# SOM_EVAL_BOARD_V100.net
KiCad netlist of a schematic drawn in EAGLE
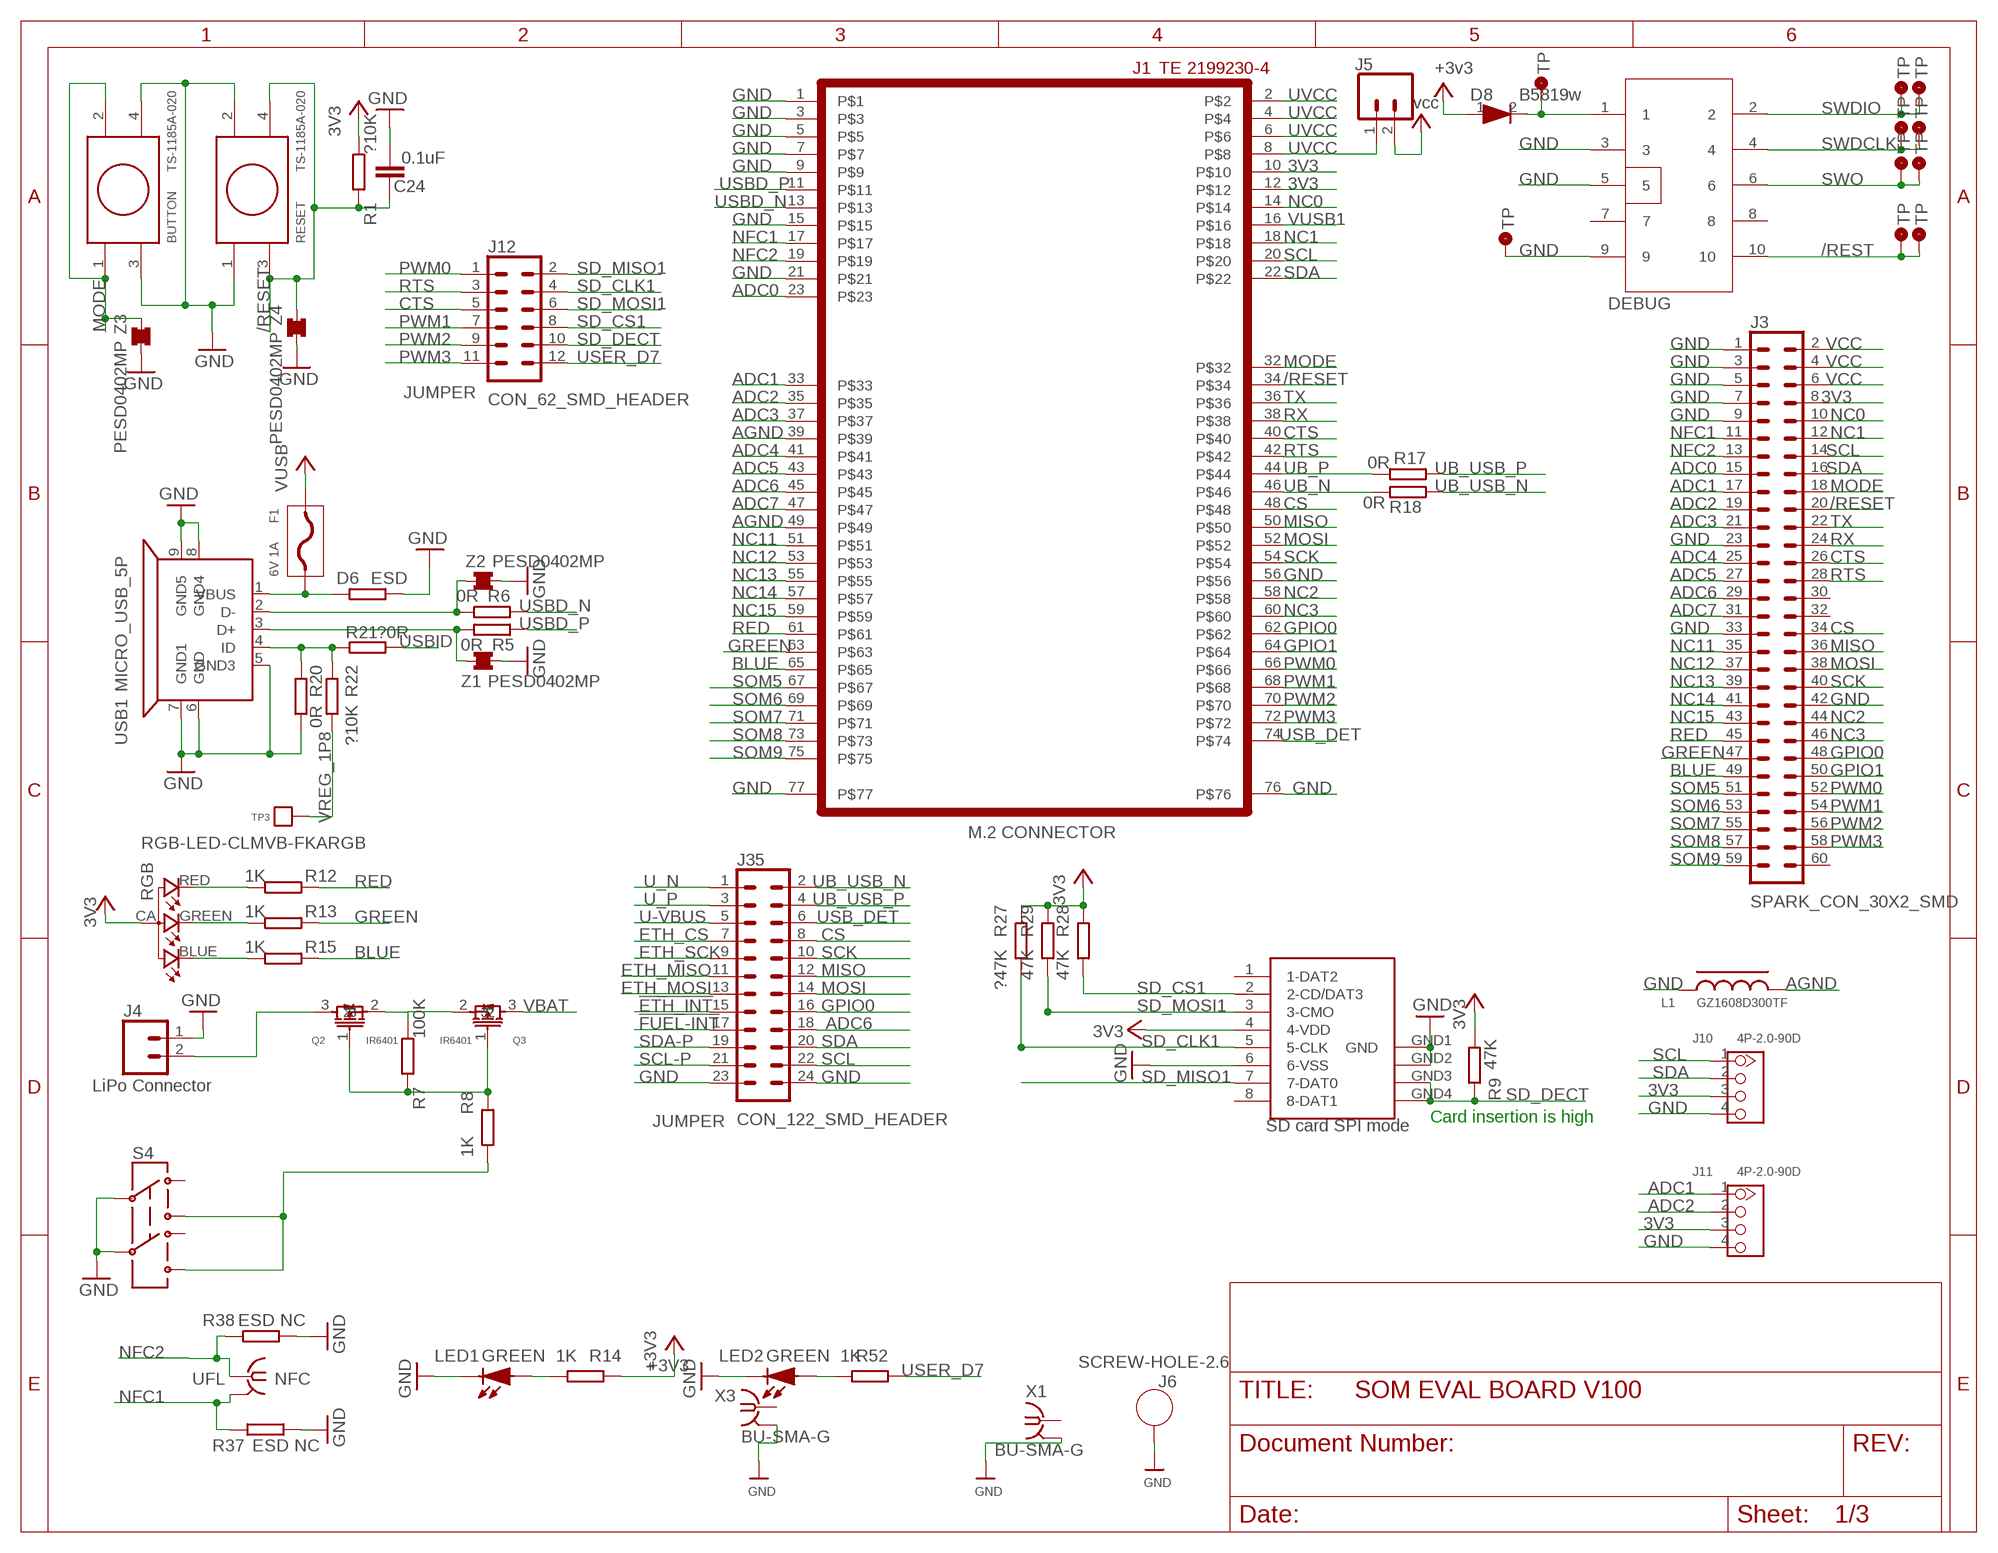
[diagram p0: schematic, sheet 1]
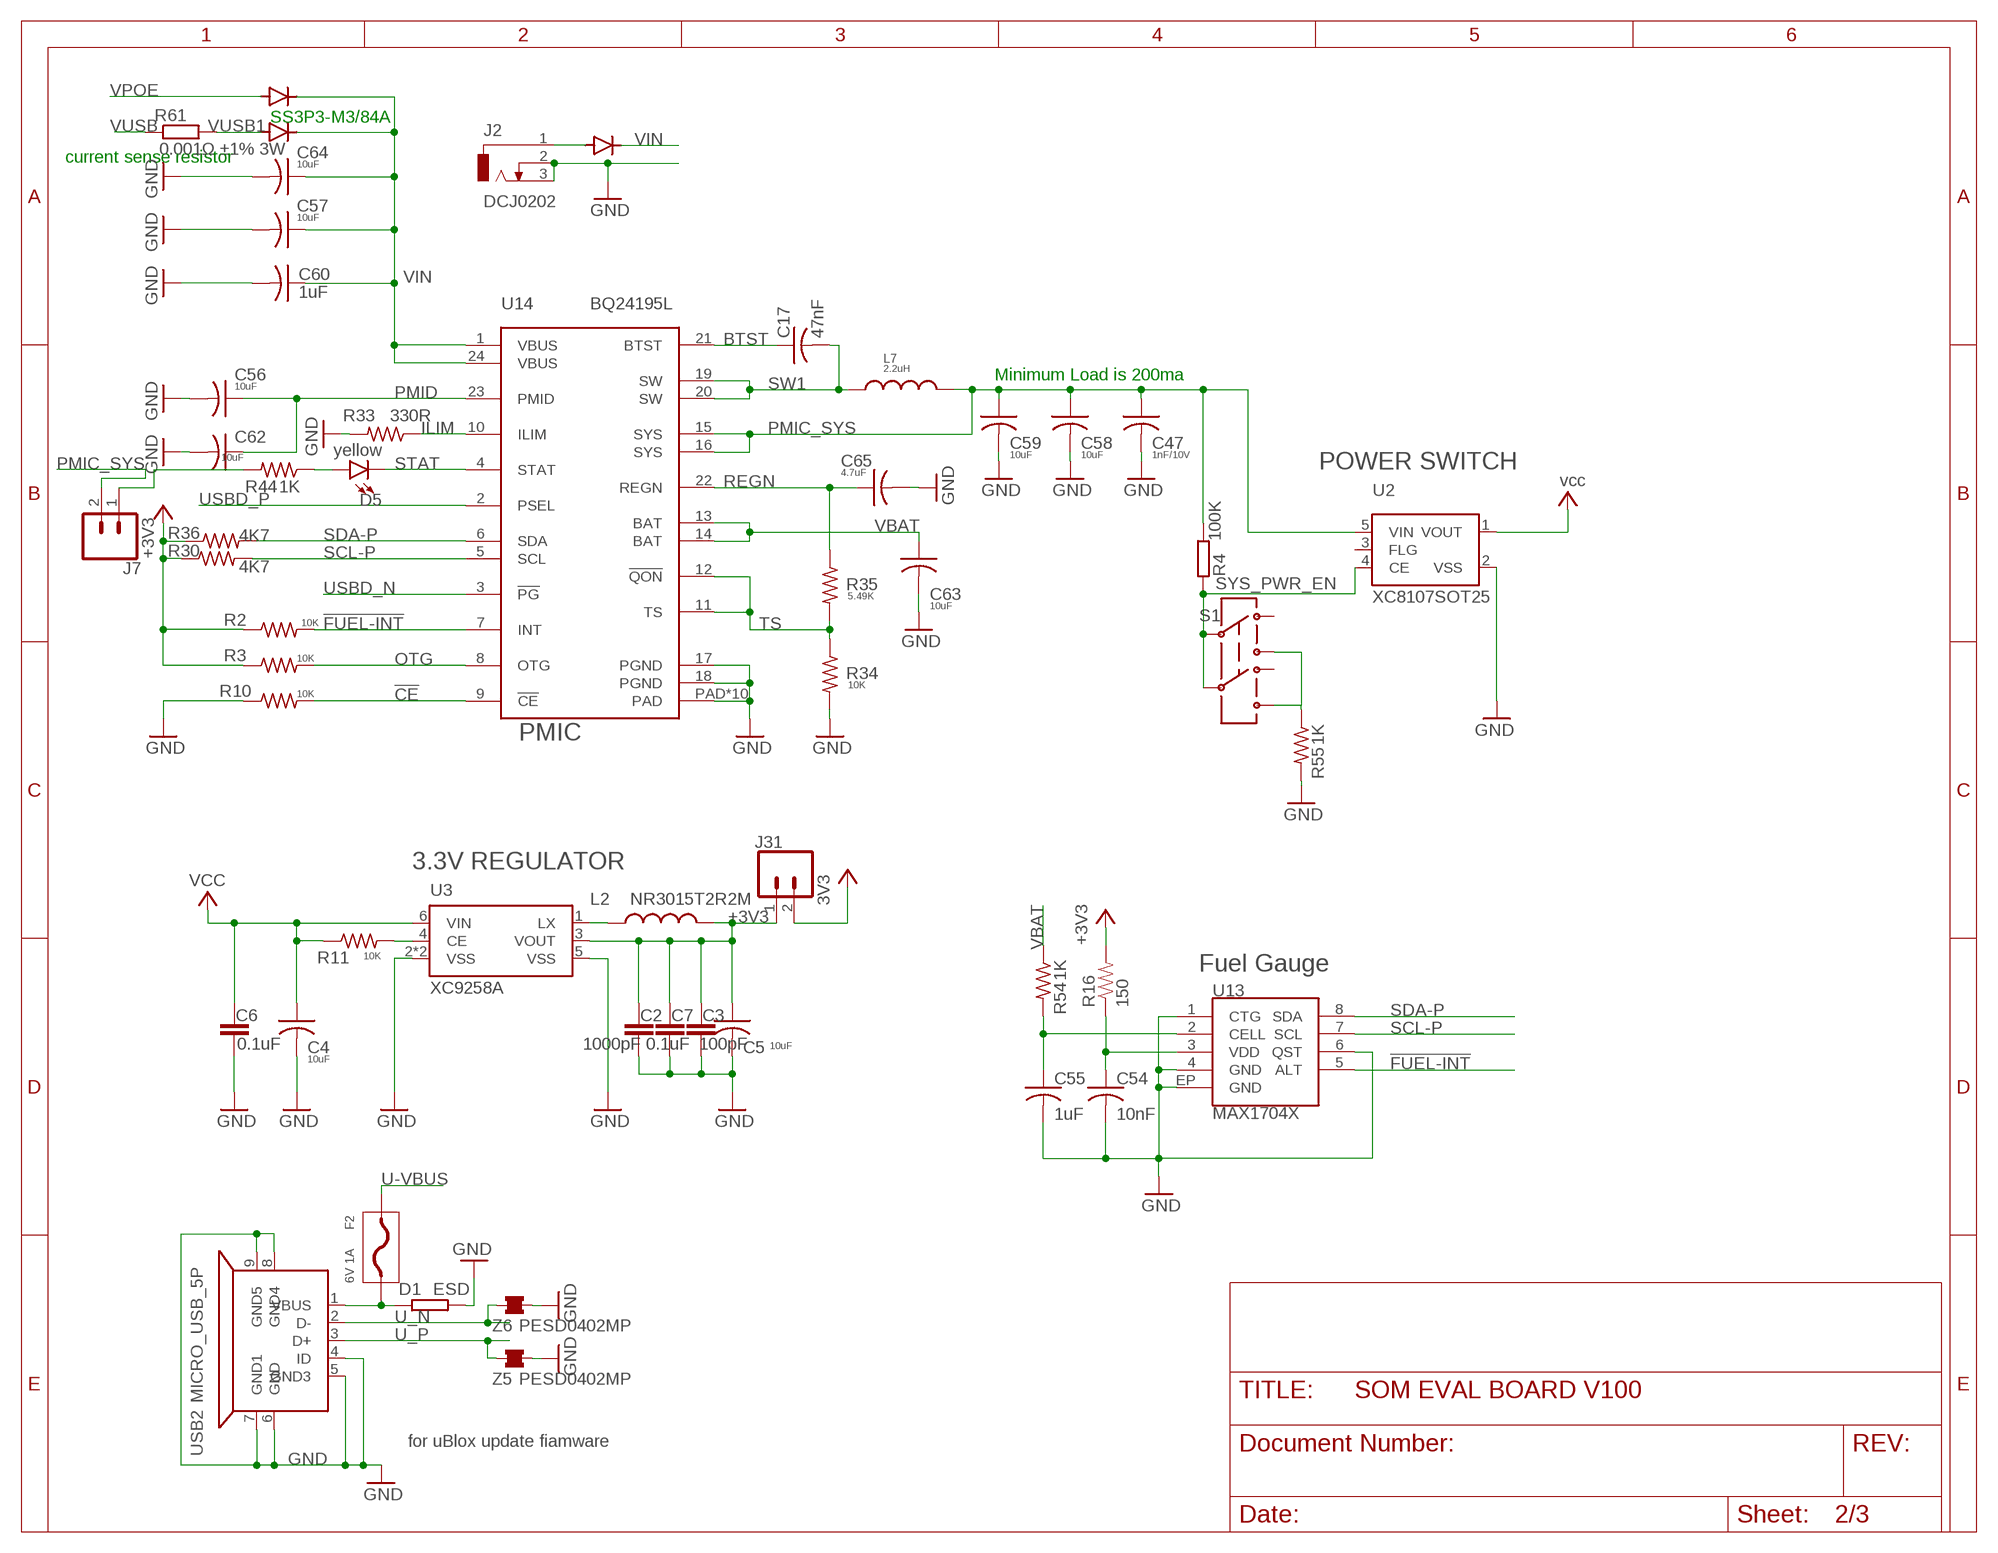
[diagram p1: schematic, sheet 2]
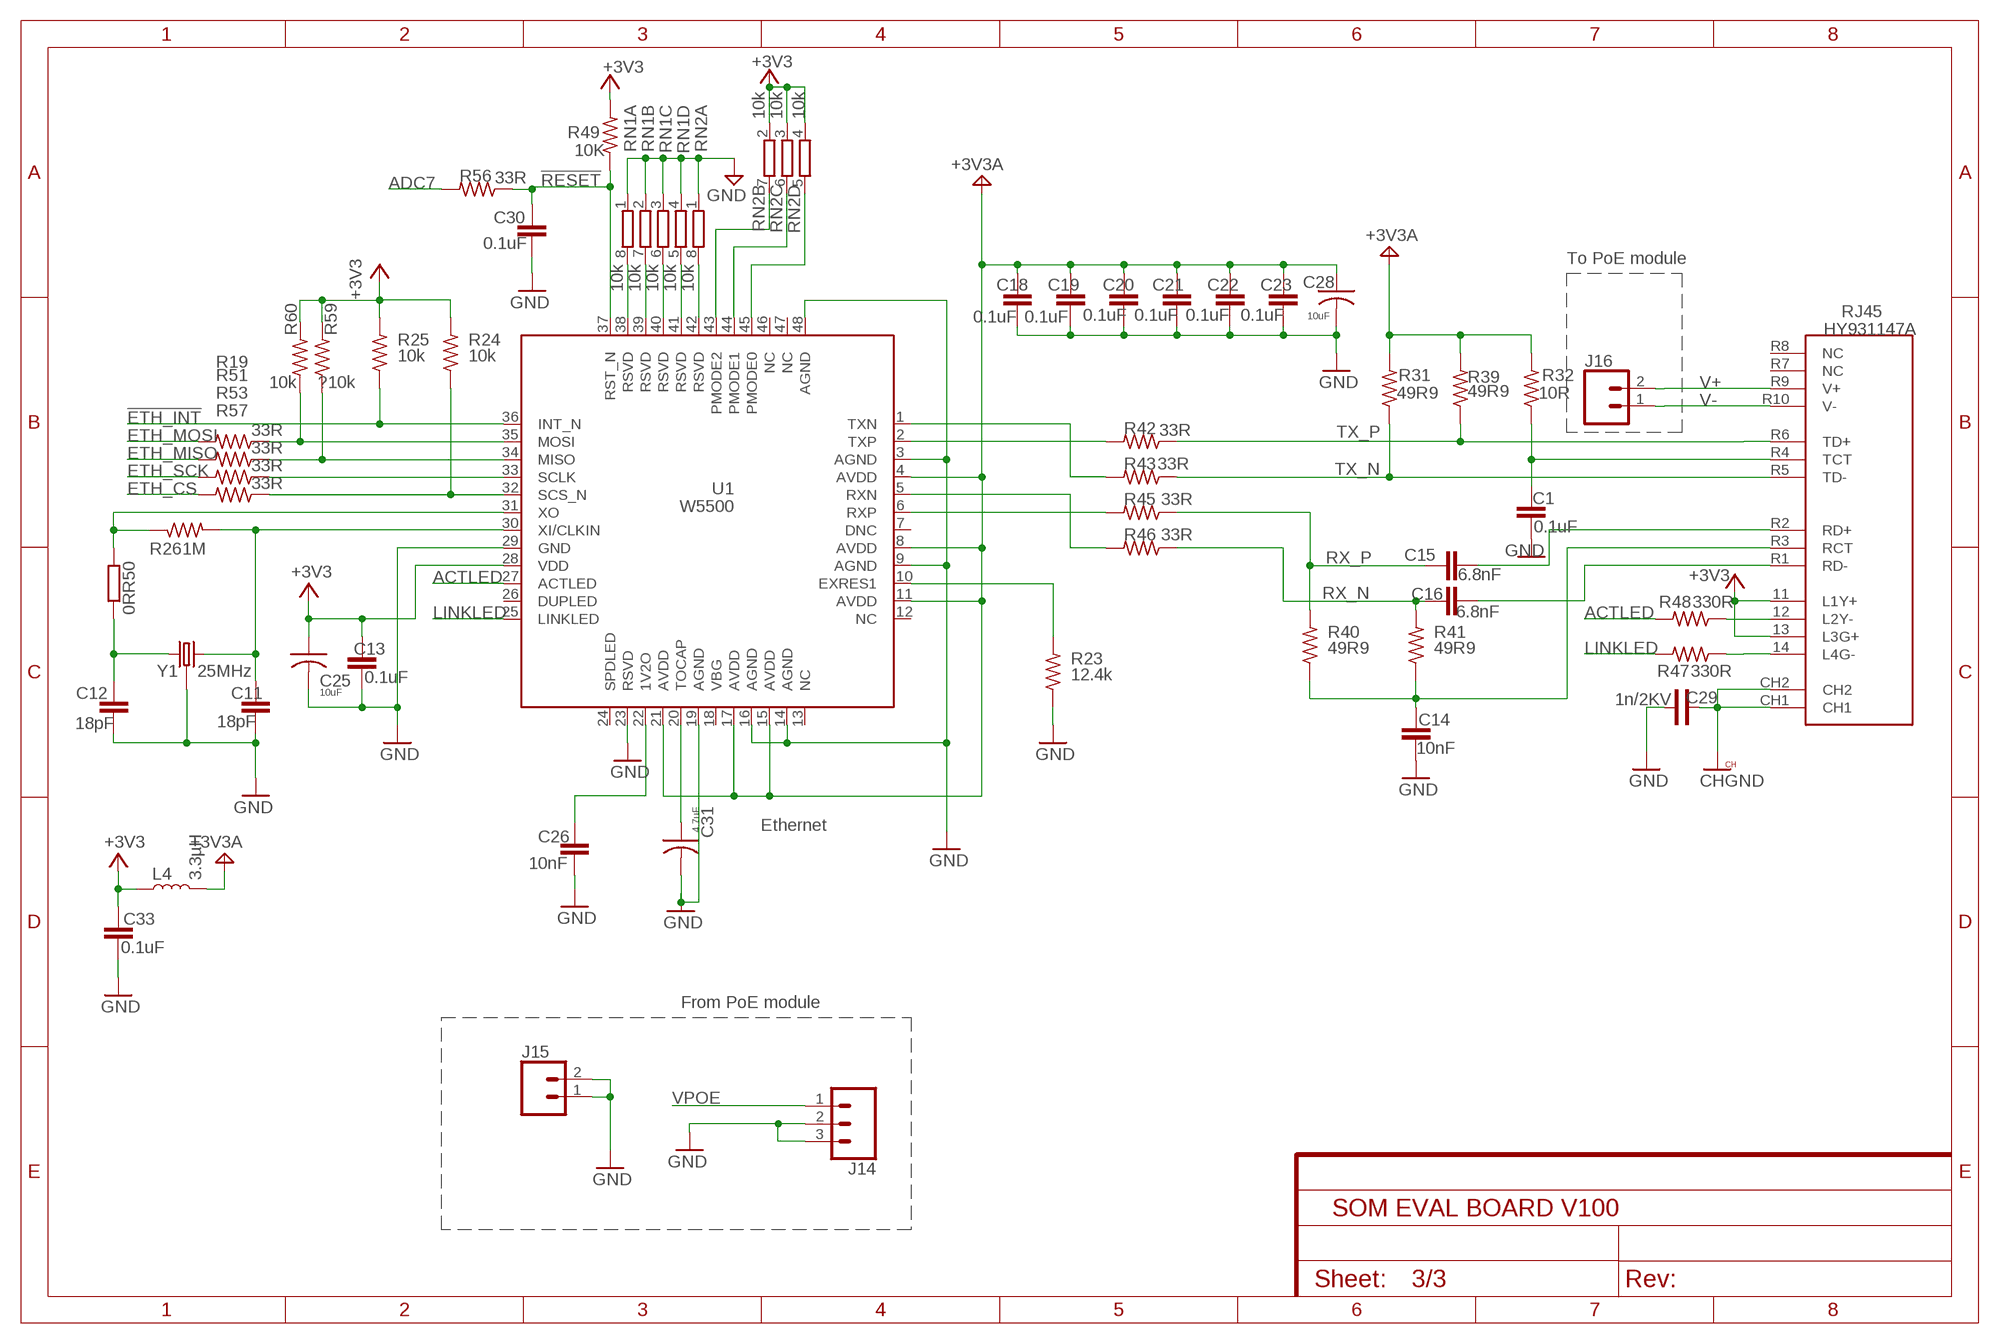
[diagram p2: schematic, sheet 3]

(export (version "E")
  (design (tool "Eeschema 10.0.6"))
  (components
    (comp (ref "C1")
      (value "0.1uF")
      (footprint "eagle-import:C0402_B")
      (libsource (lib "eagle-import") (part "CAP_1"))
    )
    (comp (ref "C11")
      (value "18pF")
      (footprint "eagle-import:C0402_B")
      (libsource (lib "eagle-import") (part "CAP_1"))
    )
    (comp (ref "C12")
      (value "18pF")
      (footprint "eagle-import:C0402_B")
      (libsource (lib "eagle-import") (part "CAP_1"))
    )
    (comp (ref "C13")
      (value "0.1uF")
      (footprint "eagle-import:C0402_B")
      (libsource (lib "eagle-import") (part "CAP_1"))
    )
    (comp (ref "C14")
      (value "10nF")
      (footprint "eagle-import:C0402_B")
      (libsource (lib "eagle-import") (part "CAP_1"))
    )
    (comp (ref "C15")
      (value "6.8nF")
      (footprint "eagle-import:C0402_B")
      (libsource (lib "eagle-import") (part "CAP_1"))
    )
    (comp (ref "C16")
      (value "6.8nF")
      (footprint "eagle-import:C0402_B")
      (libsource (lib "eagle-import") (part "CAP_1"))
    )
    (comp (ref "C18")
      (value "0.1uF")
      (footprint "eagle-import:C0402_B")
      (libsource (lib "eagle-import") (part "CAP_1"))
    )
    (comp (ref "C19")
      (value "0.1uF")
      (footprint "eagle-import:C0402_B")
      (libsource (lib "eagle-import") (part "CAP_1"))
    )
    (comp (ref "C20")
      (value "0.1uF")
      (footprint "eagle-import:C0402_B")
      (libsource (lib "eagle-import") (part "CAP_1"))
    )
    (comp (ref "C21")
      (value "0.1uF")
      (footprint "eagle-import:C0402_B")
      (libsource (lib "eagle-import") (part "CAP_1"))
    )
    (comp (ref "C22")
      (value "0.1uF")
      (footprint "eagle-import:C0402_B")
      (libsource (lib "eagle-import") (part "CAP_1"))
    )
    (comp (ref "C23")
      (value "0.1uF")
      (footprint "eagle-import:C0402_B")
      (libsource (lib "eagle-import") (part "CAP_1"))
    )
    (comp (ref "C25")
      (value "10uF")
      (footprint "eagle-import:C0603_B")
      (libsource (lib "eagle-import") (part "C-US0603"))
    )
    (comp (ref "C26")
      (value "10nF")
      (footprint "eagle-import:C0402_B")
      (libsource (lib "eagle-import") (part "CAP_1"))
    )
    (comp (ref "C28")
      (value "10uF")
      (footprint "eagle-import:C0603_B")
      (libsource (lib "eagle-import") (part "C-US0603"))
    )
    (comp (ref "C29")
      (value "1n/2KV")
      (footprint "eagle-import:C-1808")
      (libsource (lib "eagle-import") (part "C-1808"))
    )
    (comp (ref "C30")
      (value "0.1uF")
      (footprint "eagle-import:C0402_B")
      (libsource (lib "eagle-import") (part "CAP_1"))
    )
    (comp (ref "C31")
      (value "4.7uF")
      (footprint "eagle-import:C0603_B")
      (libsource (lib "eagle-import") (part "C-US0603"))
    )
    (comp (ref "C33")
      (value "0.1uF")
      (footprint "eagle-import:C0402_B")
      (libsource (lib "eagle-import") (part "CAP_1"))
    )
    (comp (ref "J14")
      (value "CONN_03")
      (footprint "eagle-import:1X03")
      (libsource (lib "eagle-import") (part "CONN_03"))
    )
    (comp (ref "J15")
      (value "CONN_02")
      (footprint "eagle-import:1X02")
      (libsource (lib "eagle-import") (part "SparkFun-Connectors_513_CONN_02"))
    )
    (comp (ref "J16")
      (value "CONN_02")
      (footprint "eagle-import:1X02")
      (libsource (lib "eagle-import") (part "SparkFun-Connectors_513_CONN_02"))
    )
    (comp (ref "L4")
      (value "3.3µH")
      (footprint "eagle-import:0805")
      (libsource (lib "eagle-import") (part "INDUCTOR-0805-3.3UH"))
    )
    (comp (ref "R19")
      (value "33R")
      (footprint "eagle-import:R0402_B")
      (libsource (lib "eagle-import") (part "R-US_"))
    )
    (comp (ref "R23")
      (value "12.4k")
      (footprint "eagle-import:R0402_B")
      (libsource (lib "eagle-import") (part "R-US_"))
    )
    (comp (ref "R24")
      (value "10k")
      (footprint "eagle-import:R0402_B")
      (libsource (lib "eagle-import") (part "R-US_"))
    )
    (comp (ref "R25")
      (value "10k")
      (footprint "eagle-import:R0402_B")
      (libsource (lib "eagle-import") (part "R-US_"))
    )
    (comp (ref "R26")
      (value "1M")
      (footprint "eagle-import:R0402_B")
      (libsource (lib "eagle-import") (part "R-US_"))
    )
    (comp (ref "R31")
      (value "49R9")
      (footprint "eagle-import:R0402_B")
      (libsource (lib "eagle-import") (part "R-US_"))
    )
    (comp (ref "R32")
      (value "10R")
      (footprint "eagle-import:R0402_B")
      (libsource (lib "eagle-import") (part "R-US_"))
    )
    (comp (ref "R39")
      (value "49R9")
      (footprint "eagle-import:R0402_B")
      (libsource (lib "eagle-import") (part "R-US_"))
    )
    (comp (ref "R40")
      (value "49R9")
      (footprint "eagle-import:R0402_B")
      (libsource (lib "eagle-import") (part "R-US_"))
    )
    (comp (ref "R41")
      (value "49R9")
      (footprint "eagle-import:R0402_B")
      (libsource (lib "eagle-import") (part "R-US_"))
    )
    (comp (ref "R42")
      (value "33R")
      (footprint "eagle-import:R0402_B")
      (libsource (lib "eagle-import") (part "R-US_"))
    )
    (comp (ref "R43")
      (value "33R")
      (footprint "eagle-import:R0402_B")
      (libsource (lib "eagle-import") (part "R-US_"))
    )
    (comp (ref "R45")
      (value "33R")
      (footprint "eagle-import:R0402_B")
      (libsource (lib "eagle-import") (part "R-US_"))
    )
    (comp (ref "R46")
      (value "33R")
      (footprint "eagle-import:R0402_B")
      (libsource (lib "eagle-import") (part "R-US_"))
    )
    (comp (ref "R47")
      (value "330R")
      (footprint "eagle-import:R0402_B")
      (libsource (lib "eagle-import") (part "R-US_"))
    )
    (comp (ref "R48")
      (value "330R")
      (footprint "eagle-import:R0402_B")
      (libsource (lib "eagle-import") (part "R-US_"))
    )
    (comp (ref "R49")
      (value "10K")
      (footprint "eagle-import:R0402_B")
      (libsource (lib "eagle-import") (part "R-US_"))
    )
    (comp (ref "R50")
      (value "0R")
      (footprint "eagle-import:R-0402S")
      (libsource (lib "eagle-import") (part "RES0402S"))
    )
    (comp (ref "R51")
      (value "33R")
      (footprint "eagle-import:R0402_B")
      (libsource (lib "eagle-import") (part "R-US_"))
    )
    (comp (ref "R53")
      (value "33R")
      (footprint "eagle-import:R0402_B")
      (libsource (lib "eagle-import") (part "R-US_"))
    )
    (comp (ref "R56")
      (value "33R")
      (footprint "eagle-import:R0402_B")
      (libsource (lib "eagle-import") (part "R-US_"))
    )
    (comp (ref "R57")
      (value "33R")
      (footprint "eagle-import:R0402_B")
      (libsource (lib "eagle-import") (part "R-US_"))
    )
    (comp (ref "R59")
      (value "?10k")
      (footprint "eagle-import:R0402_B")
      (libsource (lib "eagle-import") (part "R-US_"))
    )
    (comp (ref "R60")
      (value "10k")
      (footprint "eagle-import:R0402_B")
      (libsource (lib "eagle-import") (part "R-US_"))
    )
    (comp (ref "RJ45")
      (value "HY931147A")
      (footprint "eagle-import:ARDUINO-ETHERNET-SHIELD2-V2_CONNETTORI_POE-RJ45")
      (libsource (lib "eagle-import") (part "ARDUINO-ETHERNET-SHIELD2-V2_POE_RJ45"))
    )
    (comp (ref "RN1")
      (value "10k")
      (footprint "eagle-import:4X0402ARV341")
      (libsource (lib "eagle-import") (part "4R-N0402ARV341"))
    )
    (comp (ref "RN2")
      (value "10k")
      (footprint "eagle-import:4X0402ARV341")
      (libsource (lib "eagle-import") (part "4R-N0402ARV341"))
    )
    (comp (ref "U1")
      (value "W5500")
      (footprint "eagle-import:W5500")
      (libsource (lib "eagle-import") (part "W5500"))
    )
    (comp (ref "Y1")
      (value "25MHz")
      (footprint "eagle-import:CRYSTAL-SMD-3.2X2.5MM")
      (libsource (lib "eagle-import") (part "CRYSTAL-GROUNDEDSMD-3.2X2.5"))
    )
    (comp (ref "C2")
      (value "1000pF")
      (footprint "eagle-import:C0402_B")
      (libsource (lib "eagle-import") (part "CAP_1"))
    )
    (comp (ref "C3")
      (value "100pF")
      (footprint "eagle-import:C0402_B")
      (libsource (lib "eagle-import") (part "CAP_1"))
    )
    (comp (ref "C4")
      (value "10uF")
      (footprint "eagle-import:C0603_B")
      (libsource (lib "eagle-import") (part "C-US0603"))
    )
    (comp (ref "C5")
      (value "10uF")
      (footprint "eagle-import:C0603_B")
      (libsource (lib "eagle-import") (part "C-US0603"))
    )
    (comp (ref "C6")
      (value "0.1uF")
      (footprint "eagle-import:C0402_B")
      (libsource (lib "eagle-import") (part "CAP_1"))
    )
    (comp (ref "C7")
      (value "0.1uF")
      (footprint "eagle-import:C0402_B")
      (libsource (lib "eagle-import") (part "CAP_1"))
    )
    (comp (ref "C17")
      (value "47nF")
      (footprint "eagle-import:C0201_B")
      (libsource (lib "eagle-import") (part "C-USC0201_B"))
    )
    (comp (ref "C47")
      (value "1nF/10V")
      (footprint "eagle-import:C0402_B")
      (libsource (lib "eagle-import") (part "C-US0402"))
    )
    (comp (ref "C54")
      (value "10nF")
      (footprint "eagle-import:C0402_B")
      (libsource (lib "eagle-import") (part "Spark_C-US"))
    )
    (comp (ref "C55")
      (value "1uF")
      (footprint "eagle-import:C0402_B")
      (libsource (lib "eagle-import") (part "Spark_C-US"))
    )
    (comp (ref "C56")
      (value "10uF")
      (footprint "eagle-import:C0603_B")
      (libsource (lib "eagle-import") (part "C-US0603"))
    )
    (comp (ref "C57")
      (value "10uF")
      (footprint "eagle-import:C0603_B")
      (libsource (lib "eagle-import") (part "C-US0603"))
    )
    (comp (ref "C58")
      (value "10uF")
      (footprint "eagle-import:C0603_B")
      (libsource (lib "eagle-import") (part "C-US0603"))
    )
    (comp (ref "C59")
      (value "10uF")
      (footprint "eagle-import:C0603_B")
      (libsource (lib "eagle-import") (part "C-US0603"))
    )
    (comp (ref "C60")
      (value "1uF")
      (footprint "eagle-import:C0402_B")
      (libsource (lib "eagle-import") (part "Spark_C-US"))
    )
    (comp (ref "C62")
      (value "10uF")
      (footprint "eagle-import:C0603_B")
      (libsource (lib "eagle-import") (part "C-US0603"))
    )
    (comp (ref "C63")
      (value "10uF")
      (footprint "eagle-import:C0603_B")
      (libsource (lib "eagle-import") (part "C-US0603"))
    )
    (comp (ref "C64")
      (value "10uF")
      (footprint "eagle-import:C0603_B")
      (libsource (lib "eagle-import") (part "C-US0603"))
    )
    (comp (ref "C65")
      (value "4.7uF")
      (footprint "eagle-import:C0603_B")
      (libsource (lib "eagle-import") (part "C-US0603"))
    )
    (comp (ref "D1")
      (value "ESD")
      (footprint "eagle-import:R-0402S")
      (libsource (lib "eagle-import") (part "RES0402S"))
    )
    (comp (ref "D3")
      (value "SS3P3-M3/84A")
      (footprint "eagle-import:DIODE-DO-220AA_NT(SMP)")
      (libsource (lib "eagle-import") (part "DIODE_NT"))
    )
    (comp (ref "D4")
      (value "SS3P3-M3/84A")
      (footprint "eagle-import:DIODE-DO-220AA_NT(SMP)")
      (libsource (lib "eagle-import") (part "DIODE_NT"))
    )
    (comp (ref "D5")
      (value "yellow")
      (footprint "eagle-import:LED-0603")
      (libsource (lib "eagle-import") (part "LED-RED0603"))
    )
    (comp (ref "D7")
      (value "SS3P3-M3/84A")
      (footprint "eagle-import:DIODE-DO-220AA_NT(SMP)")
      (libsource (lib "eagle-import") (part "DIODE_NT"))
    )
    (comp (ref "F2")
      (value "6V 1A")
      (footprint "eagle-import:F0805")
      (libsource (lib "eagle-import") (part "FUSE"))
    )
    (comp (ref "J2")
      (value "DCJ0202")
      (footprint "eagle-import:DCJ0202")
      (libsource (lib "eagle-import") (part "DCJ0202"))
    )
    (comp (ref "J7")
      (value "CONN_02")
      (footprint "eagle-import:1X02")
      (libsource (lib "eagle-import") (part "SparkFun-Connectors_513_CONN_02"))
    )
    (comp (ref "J31")
      (value "CONN_02")
      (footprint "eagle-import:1X02")
      (libsource (lib "eagle-import") (part "SparkFun-Connectors_513_CONN_02"))
    )
    (comp (ref "L2")
      (value "NR3015T2R2M")
      (footprint "eagle-import:INDUCTOR-VLS-E")
      (libsource (lib "eagle-import") (part "INDUCTOR-SPARKFUNVLS3012ET-4R7M"))
    )
    (comp (ref "L7")
      (value "2.2uH")
      (footprint "eagle-import:INDUCTOR-4040")
      (libsource (lib "eagle-import") (part "INDUCTORI"))
    )
    (comp (ref "R2")
      (value "10K")
      (footprint "eagle-import:R0402_B")
      (libsource (lib "eagle-import") (part "Spark_R-US_"))
    )
    (comp (ref "R3")
      (value "10K")
      (footprint "eagle-import:R0402_B")
      (libsource (lib "eagle-import") (part "Spark_R-US_"))
    )
    (comp (ref "R4")
      (value "100K")
      (footprint "eagle-import:R0603")
      (libsource (lib "eagle-import") (part "RESR0603"))
    )
    (comp (ref "R10")
      (value "10K")
      (footprint "eagle-import:R0402_B")
      (libsource (lib "eagle-import") (part "Spark_R-US_"))
    )
    (comp (ref "R11")
      (value "10K")
      (footprint "eagle-import:R0402_B")
      (libsource (lib "eagle-import") (part "Spark_R-US_"))
    )
    (comp (ref "R16")
      (value "150")
      (footprint "eagle-import:0402-RES")
      (libsource (lib "eagle-import") (part "RESISTOR0402-RES"))
    )
    (comp (ref "R30")
      (value "4K7")
      (footprint "eagle-import:C0201_B")
      (libsource (lib "eagle-import") (part "R-US_R0201_B"))
    )
    (comp (ref "R33")
      (value "330R")
      (footprint "eagle-import:R0402_B")
      (libsource (lib "eagle-import") (part "R-US_"))
    )
    (comp (ref "R34")
      (value "10K")
      (footprint "eagle-import:R0402_B")
      (libsource (lib "eagle-import") (part "Spark_R-US_"))
    )
    (comp (ref "R35")
      (value "5.49K")
      (footprint "eagle-import:R0402_B")
      (libsource (lib "eagle-import") (part "Spark_R-US_"))
    )
    (comp (ref "R36")
      (value "4K7")
      (footprint "eagle-import:C0201_B")
      (libsource (lib "eagle-import") (part "R-US_R0201_B"))
    )
    (comp (ref "R44")
      (value "1K")
      (footprint "eagle-import:R0402_B")
      (libsource (lib "eagle-import") (part "R-US_"))
    )
    (comp (ref "R54")
      (value "1K")
      (footprint "eagle-import:R0402_B")
      (libsource (lib "eagle-import") (part "R-US_"))
    )
    (comp (ref "R55")
      (value "1K")
      (footprint "eagle-import:R0402_B")
      (libsource (lib "eagle-import") (part "R-US_"))
    )
    (comp (ref "R61")
      (value "0.001Ω ±1% 3W")
      (footprint "eagle-import:R2512")
      (libsource (lib "eagle-import") (part "R-EU_R2512"))
    )
    (comp (ref "S1")
      (value "SWITCH-DPDT")
      (footprint "eagle-import:SWITCH-2.5X3.2-6")
      (libsource (lib "eagle-import") (part "SWITCH-DPDT"))
    )
    (comp (ref "U2")
      (value "XC8107SOT25")
      (footprint "eagle-import:SOT25")
      (libsource (lib "eagle-import") (part "XC8107SOT25"))
    )
    (comp (ref "U3")
      (value "XC9258A")
      (footprint "eagle-import:USP-6C")
      (libsource (lib "eagle-import") (part "XC9258A33EER-G"))
    )
    (comp (ref "U13")
      (value "MAX1704X")
      (footprint "eagle-import:TDFN-8")
      (libsource (lib "eagle-import") (part "MAX1704X"))
    )
    (comp (ref "U14")
      (value "BQ24195L")
      (footprint "eagle-import:QFN24")
      (libsource (lib "eagle-import") (part "BQ24298RTWR"))
    )
    (comp (ref "USB2")
      (value "MICRO_USB_5P")
      (footprint "eagle-import:MICRO_USB")
      (libsource (lib "eagle-import") (part "MICRO_USBMICRO_USB"))
    )
    (comp (ref "Z5")
      (value "PESD0402MP")
      (footprint "eagle-import:SMD-0402MP")
      (libsource (lib "eagle-import") (part "PESD0402MP"))
    )
    (comp (ref "Z6")
      (value "PESD0402MP")
      (footprint "eagle-import:SMD-0402MP")
      (libsource (lib "eagle-import") (part "PESD0402MP"))
    )
    (comp (ref "BUTTON")
      (value "TS-1185A-020")
      (footprint "eagle-import:TS-1185A-020")
      (libsource (lib "eagle-import") (part "TS-1185A-020"))
    )
    (comp (ref "C24")
      (value "0.1uF")
      (footprint "eagle-import:C0402_B")
      (libsource (lib "eagle-import") (part "CAP_1"))
    )
    (comp (ref "D6")
      (value "ESD")
      (footprint "eagle-import:R-0402S")
      (libsource (lib "eagle-import") (part "RES0402S"))
    )
    (comp (ref "D8")
      (value "B5819w")
      (footprint "eagle-import:SOD-123")
      (libsource (lib "eagle-import") (part "DIODESOD123"))
    )
    (comp (ref "DEBUG")
      (value "CON5X2")
      (footprint "eagle-import:CON5X2_1.27")
      (libsource (lib "eagle-import") (part "CON5X2"))
    )
    (comp (ref "F1")
      (value "6V 1A")
      (footprint "eagle-import:F0805")
      (libsource (lib "eagle-import") (part "FUSE"))
    )
    (comp (ref "J1")
      (value "TE 2199230-4")
      (footprint "eagle-import:M.2EKEY")
      (libsource (lib "eagle-import") (part "M.2EKEY"))
    )
    (comp (ref "J3")
      (value "SPARK_CON_30X2_SMD")
      (footprint "eagle-import:SPARK_CON_30X2_SMD")
      (libsource (lib "eagle-import") (part "SPARK_CON_30X2_SMD"))
    )
    (comp (ref "J4")
      (value "CONN_02-JST-2MM-SMT")
      (footprint "eagle-import:JST-2-SMD")
      (libsource (lib "eagle-import") (part "CONN_02-JST-2MM-SMT"))
    )
    (comp (ref "J5")
      (value "CONN_02")
      (footprint "eagle-import:1X02")
      (libsource (lib "eagle-import") (part "SparkFun-Connectors_513_CONN_02"))
    )
    (comp (ref "J6")
      (value "SCREW-HOLE-2.6")
      (footprint "eagle-import:SCREW-HOLE-2.6")
      (libsource (lib "eagle-import") (part "SCREW-HOLE-2.6"))
    )
    (comp (ref "J10")
      (value "4P-2.0-90D")
      (footprint "eagle-import:HW4-2.0-90D")
      (libsource (lib "eagle-import") (part "GROVE-CONNECTOR-DIP-90D(4P-2.0)"))
    )
    (comp (ref "J11")
      (value "4P-2.0-90D")
      (footprint "eagle-import:HW4-2.0-90D")
      (libsource (lib "eagle-import") (part "GROVE-CONNECTOR-DIP-90D(4P-2.0)"))
    )
    (comp (ref "J12")
      (value "CON_62_SMD_HEADER")
      (footprint "eagle-import:CON_6_2_SMD_HEADER")
      (libsource (lib "eagle-import") (part "CON_62_SMD_HEADER"))
    )
    (comp (ref "J35")
      (value "CON_122_SMD_HEADER")
      (footprint "eagle-import:CON_12_2_SMD_HEADER")
      (libsource (lib "eagle-import") (part "CON_122_SMD_HEADER"))
    )
    (comp (ref "L1")
      (value "GZ1608D300TF")
      (footprint "eagle-import:R-0603A")
      (libsource (lib "eagle-import") (part "L"))
    )
    (comp (ref "LED1")
      (value "GREEN")
      (footprint "eagle-import:LED0603")
      (libsource (lib "eagle-import") (part "LED"))
    )
    (comp (ref "LED2")
      (value "GREEN")
      (footprint "eagle-import:LED0603")
      (libsource (lib "eagle-import") (part "LED"))
    )
    (comp (ref "NFC")
      (value "UFL")
      (footprint "eagle-import:IPEX-20279-001E")
      (libsource (lib "eagle-import") (part "IPEX-20279-001E"))
    )
    (comp (ref "P1")
      (value "SPARK_POGOPIN")
      (footprint "eagle-import:SPARK_POGO-2.0")
      (libsource (lib "eagle-import") (part "SPARK_POGOPIN"))
    )
    (comp (ref "P2")
      (value "SPARK_POGOPIN")
      (footprint "eagle-import:SPARK_POGO-2.0")
      (libsource (lib "eagle-import") (part "SPARK_POGOPIN"))
    )
    (comp (ref "P3")
      (value "SPARK_POGOPIN")
      (footprint "eagle-import:SPARK_POGO-2.0")
      (libsource (lib "eagle-import") (part "SPARK_POGOPIN"))
    )
    (comp (ref "P4")
      (value "SPARK_POGOPIN")
      (footprint "eagle-import:SPARK_POGO-2.0")
      (libsource (lib "eagle-import") (part "SPARK_POGOPIN"))
    )
    (comp (ref "Q2")
      (value "IR6401")
      (footprint "eagle-import:SOT-23")
      (libsource (lib "eagle-import") (part "PMOS"))
    )
    (comp (ref "Q3")
      (value "IR6401")
      (footprint "eagle-import:SOT-23")
      (libsource (lib "eagle-import") (part "PMOS"))
    )
    (comp (ref "R1")
      (value "?10K")
      (footprint "eagle-import:R-0402S")
      (libsource (lib "eagle-import") (part "RES0402S"))
    )
    (comp (ref "R5")
      (value "0R")
      (footprint "eagle-import:R-0402S")
      (libsource (lib "eagle-import") (part "RES0402S"))
    )
    (comp (ref "R6")
      (value "0R")
      (footprint "eagle-import:R-0402S")
      (libsource (lib "eagle-import") (part "RES0402S"))
    )
    (comp (ref "R7")
      (value "100K")
      (footprint "eagle-import:R0603")
      (libsource (lib "eagle-import") (part "RESR0603"))
    )
    (comp (ref "R8")
      (value "1K")
      (footprint "eagle-import:R-0402S")
      (libsource (lib "eagle-import") (part "RES0402S"))
    )
    (comp (ref "R9")
      (value "47K")
      (footprint "eagle-import:R-0402S")
      (libsource (lib "eagle-import") (part "RES0402S"))
    )
    (comp (ref "R12")
      (value "1K")
      (footprint "eagle-import:R-0402S")
      (libsource (lib "eagle-import") (part "RES0402S"))
    )
    (comp (ref "R13")
      (value "1K")
      (footprint "eagle-import:R-0402S")
      (libsource (lib "eagle-import") (part "RES0402S"))
    )
    (comp (ref "R14")
      (value "1K")
      (footprint "eagle-import:R-0402S")
      (libsource (lib "eagle-import") (part "RES0402S"))
    )
    (comp (ref "R15")
      (value "1K")
      (footprint "eagle-import:R-0402S")
      (libsource (lib "eagle-import") (part "RES0402S"))
    )
    (comp (ref "R17")
      (value "0R")
      (footprint "eagle-import:R-0402S")
      (libsource (lib "eagle-import") (part "RES0402S"))
    )
    (comp (ref "R18")
      (value "0R")
      (footprint "eagle-import:R-0402S")
      (libsource (lib "eagle-import") (part "RES0402S"))
    )
    (comp (ref "R20")
      (value "0R")
      (footprint "eagle-import:R-0402S")
      (libsource (lib "eagle-import") (part "RES0402S"))
    )
    (comp (ref "R21")
      (value "?0R")
      (footprint "eagle-import:R-0402S")
      (libsource (lib "eagle-import") (part "RES0402S"))
    )
    (comp (ref "R22")
      (value "?10K")
      (footprint "eagle-import:R-0402S")
      (libsource (lib "eagle-import") (part "RES0402S"))
    )
    (comp (ref "R27")
      (value "?47K")
      (footprint "eagle-import:R-0402S")
      (libsource (lib "eagle-import") (part "RES0402S"))
    )
    (comp (ref "R28")
      (value "47K")
      (footprint "eagle-import:R-0402S")
      (libsource (lib "eagle-import") (part "RES0402S"))
    )
    (comp (ref "R29")
      (value "47K")
      (footprint "eagle-import:R-0402S")
      (libsource (lib "eagle-import") (part "RES0402S"))
    )
    (comp (ref "R37")
      (value "ESD NC")
      (footprint "eagle-import:R-0402S")
      (libsource (lib "eagle-import") (part "RES0402S"))
    )
    (comp (ref "R38")
      (value "ESD NC")
      (footprint "eagle-import:R-0402S")
      (libsource (lib "eagle-import") (part "RES0402S"))
    )
    (comp (ref "R52")
      (value "1K")
      (footprint "eagle-import:R-0402S")
      (libsource (lib "eagle-import") (part "RES0402S"))
    )
    (comp (ref "RESET")
      (value "TS-1185A-020")
      (footprint "eagle-import:TS-1185A-020")
      (libsource (lib "eagle-import") (part "TS-1185A-020"))
    )
    (comp (ref "RGB")
      (value "RGB-LED-CLMVB-FKARGB")
      (footprint "eagle-import:PLCC4-2MM-RGB")
      (libsource (lib "eagle-import") (part "RGB-LED-CLMVB-FKARGB"))
    )
    (comp (ref "S4")
      (value "SWITCH-DPDT")
      (footprint "eagle-import:SWITCH-2.5X3.2-6")
      (libsource (lib "eagle-import") (part "SWITCH-DPDT"))
    )
    (comp (ref "TP3")
      (value "TPTP")
      (footprint "eagle-import:TP")
      (libsource (lib "eagle-import") (part "TPTP"))
    )
    (comp (ref "U$1")
      (value "TP2")
      (footprint "eagle-import:TP70_BOT")
      (libsource (lib "eagle-import") (part "TP2"))
    )
    (comp (ref "U$2")
      (value "TP2")
      (footprint "eagle-import:TP70_BOT")
      (libsource (lib "eagle-import") (part "TP2"))
    )
    (comp (ref "U$9")
      (value "TP2")
      (footprint "eagle-import:TP70_BOT")
      (libsource (lib "eagle-import") (part "TP2"))
    )
    (comp (ref "U$10")
      (value "TP2")
      (footprint "eagle-import:TP70_BOT")
      (libsource (lib "eagle-import") (part "TP2"))
    )
    (comp (ref "U$11")
      (value "TP2")
      (footprint "eagle-import:TP70_BOT")
      (libsource (lib "eagle-import") (part "TP2"))
    )
    (comp (ref "U$12")
      (value "TP2")
      (footprint "eagle-import:TP70_BOT")
      (libsource (lib "eagle-import") (part "TP2"))
    )
    (comp (ref "USB1")
      (value "MICRO_USB_5P")
      (footprint "eagle-import:MICRO_USB")
      (libsource (lib "eagle-import") (part "MICRO_USBMICRO_USB"))
    )
    (comp (ref "X1")
      (value "BU-SMA-G")
      (footprint "eagle-import:BU-SMA-G")
      (libsource (lib "eagle-import") (part "BU-SMA-G"))
    )
    (comp (ref "X3")
      (value "BU-SMA-G")
      (footprint "eagle-import:BU-SMA-G")
      (libsource (lib "eagle-import") (part "BU-SMA-G"))
    )
    (comp (ref "X4")
      (value "0046_15TW-882")
      (footprint "eagle-import:SDCARD-15TW-8821")
      (fields (field (name "PART_NUMBER") "15TW-882 REEL"))
      (libsource (lib "eagle-import") (part "0046_15TW-882"))
    )
    (comp (ref "Z1")
      (value "PESD0402MP")
      (footprint "eagle-import:SMD-0402MP")
      (libsource (lib "eagle-import") (part "PESD0402MP"))
    )
    (comp (ref "Z2")
      (value "PESD0402MP")
      (footprint "eagle-import:SMD-0402MP")
      (libsource (lib "eagle-import") (part "PESD0402MP"))
    )
    (comp (ref "Z3")
      (value "PESD0402MP")
      (footprint "eagle-import:SMD-0402MP")
      (libsource (lib "eagle-import") (part "PESD0402MP"))
    )
    (comp (ref "Z4")
      (value "PESD0402MP")
      (footprint "eagle-import:SMD-0402MP")
      (libsource (lib "eagle-import") (part "PESD0402MP"))
    )
  )
  (nets
    (net (code "1") (name "+3V3") (class "Default")
      (node (ref "C13") (pin "2") (pinfunction "P$2_2") (pintype "passive"))
      (node (ref "C2") (pin "2") (pinfunction "P$2_2") (pintype "passive"))
      (node (ref "C25") (pin "1") (pinfunction "1_1") (pintype "passive"))
      (node (ref "C3") (pin "2") (pinfunction "P$2_2") (pintype "passive"))
      (node (ref "C33") (pin "2") (pinfunction "P$2_2") (pintype "passive"))
      (node (ref "C5") (pin "1") (pinfunction "1_1") (pintype "passive"))
      (node (ref "C7") (pin "2") (pinfunction "P$2_2") (pintype "passive"))
      (node (ref "D8") (pin "1") (pinfunction "P$1_1") (pintype "bidirectional"))
      (node (ref "J31") (pin "1") (pinfunction "1_1") (pintype "passive"))
      (node (ref "L2") (pin "P$2") (pinfunction "2_P$2") (pintype "passive"))
      (node (ref "L4") (pin "1") (pinfunction "1_1") (pintype "passive"))
      (node (ref "R14") (pin "1") (pinfunction "1_1") (pintype "bidirectional"))
      (node (ref "R16") (pin "2") (pinfunction "2_2") (pintype "passive"))
      (node (ref "R2") (pin "1") (pinfunction "1_1") (pintype "passive"))
      (node (ref "R24") (pin "2") (pinfunction "2_2") (pintype "passive"))
      (node (ref "R25") (pin "2") (pinfunction "2_2") (pintype "passive"))
      (node (ref "R3") (pin "1") (pinfunction "1_1") (pintype "passive"))
      (node (ref "R30") (pin "1") (pinfunction "1_1") (pintype "passive"))
      (node (ref "R36") (pin "1") (pinfunction "1_1") (pintype "passive"))
      (node (ref "R49") (pin "2") (pinfunction "2_2") (pintype "passive"))
      (node (ref "R59") (pin "2") (pinfunction "2_2") (pintype "passive"))
      (node (ref "R60") (pin "2") (pinfunction "2_2") (pintype "passive"))
      (node (ref "RJ45") (pin "11") (pinfunction "L1Y+_11") (pintype "bidirectional"))
      (node (ref "RJ45") (pin "13") (pinfunction "L3G+_13") (pintype "bidirectional"))
      (node (ref "RN2") (pin "2") (pinfunction "1_2") (pintype "passive"))
      (node (ref "RN2") (pin "3") (pinfunction "1_3") (pintype "passive"))
      (node (ref "RN2") (pin "4") (pinfunction "1_4") (pintype "passive"))
      (node (ref "U1") (pin "28") (pinfunction "VDD_28") (pintype "passive"))
      (node (ref "U3") (pin "3") (pinfunction "VOUT_3") (pintype "power_in"))
    )
    (net (code "2") (name "+3V3A") (class "Default")
      (node (ref "C18") (pin "2") (pinfunction "P$2_2") (pintype "passive"))
      (node (ref "C19") (pin "2") (pinfunction "P$2_2") (pintype "passive"))
      (node (ref "C20") (pin "2") (pinfunction "P$2_2") (pintype "passive"))
      (node (ref "C21") (pin "2") (pinfunction "P$2_2") (pintype "passive"))
      (node (ref "C22") (pin "2") (pinfunction "P$2_2") (pintype "passive"))
      (node (ref "C23") (pin "2") (pinfunction "P$2_2") (pintype "passive"))
      (node (ref "C28") (pin "1") (pinfunction "1_1") (pintype "passive"))
      (node (ref "L4") (pin "2") (pinfunction "2_2") (pintype "passive"))
      (node (ref "R31") (pin "2") (pinfunction "2_2") (pintype "passive"))
      (node (ref "R32") (pin "2") (pinfunction "2_2") (pintype "passive"))
      (node (ref "R39") (pin "2") (pinfunction "2_2") (pintype "passive"))
      (node (ref "U1") (pin "11") (pinfunction "AVDD_11") (pintype "passive"))
      (node (ref "U1") (pin "15") (pinfunction "AVDD_15") (pintype "passive"))
      (node (ref "U1") (pin "17") (pinfunction "AVDD_17") (pintype "passive"))
      (node (ref "U1") (pin "21") (pinfunction "AVDD_21") (pintype "passive"))
      (node (ref "U1") (pin "4") (pinfunction "AVDD_4") (pintype "passive"))
      (node (ref "U1") (pin "8") (pinfunction "AVDD_8") (pintype "passive"))
    )
    (net (code "3") (name "3V3") (class "Default")
      (node (ref "J1") (pin "10") (pinfunction "P$10_10") (pintype "bidirectional"))
      (node (ref "J1") (pin "12") (pinfunction "P$12_12") (pintype "bidirectional"))
      (node (ref "J10") (pin "3") (pinfunction "3_3") (pintype "bidirectional"))
      (node (ref "J11") (pin "3") (pinfunction "3_3") (pintype "bidirectional"))
      (node (ref "J3") (pin "8") (pinfunction "8_8") (pintype "passive"))
      (node (ref "J31") (pin "2") (pinfunction "2_2") (pintype "passive"))
      (node (ref "R1") (pin "2") (pinfunction "2_2") (pintype "bidirectional"))
      (node (ref "R27") (pin "1") (pinfunction "1_1") (pintype "bidirectional"))
      (node (ref "R28") (pin "1") (pinfunction "1_1") (pintype "bidirectional"))
      (node (ref "R29") (pin "1") (pinfunction "1_1") (pintype "bidirectional"))
      (node (ref "R9") (pin "2") (pinfunction "2_2") (pintype "bidirectional"))
      (node (ref "RGB") (pin "CA") (pinfunction "1_CA") (pintype "passive"))
      (node (ref "X4") (pin "4") (pinfunction "4-VDD_4") (pintype "bidirectional"))
    )
    (net (code "4") (name "ACTLED") (class "Default")
      (node (ref "R48") (pin "2") (pinfunction "2_2") (pintype "passive"))
      (node (ref "U1") (pin "27") (pinfunction "ACTLED_27") (pintype "passive"))
    )
    (net (code "5") (name "ADC0") (class "Default")
      (node (ref "J1") (pin "23") (pinfunction "P$23_23") (pintype "bidirectional"))
      (node (ref "J3") (pin "15") (pinfunction "15_15") (pintype "passive"))
    )
    (net (code "6") (name "ADC1") (class "Default")
      (node (ref "J1") (pin "33") (pinfunction "P$33_33") (pintype "bidirectional"))
      (node (ref "J11") (pin "1") (pinfunction "1_1") (pintype "bidirectional"))
      (node (ref "J3") (pin "17") (pinfunction "17_17") (pintype "passive"))
    )
    (net (code "7") (name "ADC2") (class "Default")
      (node (ref "J1") (pin "35") (pinfunction "P$35_35") (pintype "bidirectional"))
      (node (ref "J11") (pin "2") (pinfunction "2_2") (pintype "bidirectional"))
      (node (ref "J3") (pin "19") (pinfunction "19_19") (pintype "passive"))
    )
    (net (code "8") (name "ADC3") (class "Default")
      (node (ref "J1") (pin "37") (pinfunction "P$37_37") (pintype "bidirectional"))
      (node (ref "J3") (pin "21") (pinfunction "21_21") (pintype "passive"))
    )
    (net (code "9") (name "ADC4") (class "Default")
      (node (ref "J1") (pin "41") (pinfunction "P$41_41") (pintype "bidirectional"))
      (node (ref "J3") (pin "25") (pinfunction "25_25") (pintype "passive"))
    )
    (net (code "10") (name "ADC5") (class "Default")
      (node (ref "J1") (pin "43") (pinfunction "P$43_43") (pintype "bidirectional"))
      (node (ref "J3") (pin "27") (pinfunction "27_27") (pintype "passive"))
    )
    (net (code "11") (name "ADC6") (class "Default")
      (node (ref "J1") (pin "45") (pinfunction "P$45_45") (pintype "bidirectional"))
      (node (ref "J3") (pin "29") (pinfunction "29_29") (pintype "passive"))
      (node (ref "J35") (pin "18") (pinfunction "18_18") (pintype "passive"))
    )
    (net (code "12") (name "ADC7") (class "Default")
      (node (ref "J1") (pin "47") (pinfunction "P$47_47") (pintype "bidirectional"))
      (node (ref "J3") (pin "31") (pinfunction "31_31") (pintype "passive"))
      (node (ref "R56") (pin "2") (pinfunction "2_2") (pintype "passive"))
    )
    (net (code "13") (name "AGND") (class "Default")
      (node (ref "J1") (pin "39") (pinfunction "P$39_39") (pintype "bidirectional"))
      (node (ref "J1") (pin "49") (pinfunction "P$49_49") (pintype "bidirectional"))
      (node (ref "L1") (pin "2") (pinfunction "2_2") (pintype "bidirectional"))
    )
    (net (code "14") (name "BLUE") (class "Default")
      (node (ref "J1") (pin "65") (pinfunction "P$65_65") (pintype "bidirectional"))
      (node (ref "J3") (pin "49") (pinfunction "49_49") (pintype "passive"))
      (node (ref "R15") (pin "1") (pinfunction "1_1") (pintype "bidirectional"))
    )
    (net (code "15") (name "BTST") (class "Default")
      (node (ref "C17") (pin "1") (pinfunction "1_1") (pintype "passive"))
      (node (ref "U14") (pin "21") (pinfunction "BTST_21") (pintype "bidirectional"))
    )
    (net (code "16") (name "CHGND") (class "Default")
      (node (ref "C29") (pin "P$1") (pinfunction "P$1_P$1") (pintype "passive"))
      (node (ref "RJ45") (pin "CH1") (pinfunction "CH1_CH1") (pintype "bidirectional"))
      (node (ref "RJ45") (pin "CH2") (pinfunction "CH2_CH2") (pintype "bidirectional"))
    )
    (net (code "17") (name "CS") (class "Default")
      (node (ref "J1") (pin "48") (pinfunction "P$48_48") (pintype "bidirectional"))
      (node (ref "J3") (pin "34") (pinfunction "34_34") (pintype "passive"))
      (node (ref "J35") (pin "8") (pinfunction "8_8") (pintype "passive"))
    )
    (net (code "18") (name "CTS") (class "Default")
      (node (ref "J1") (pin "40") (pinfunction "P$40_40") (pintype "bidirectional"))
      (node (ref "J12") (pin "5") (pinfunction "5_5") (pintype "passive"))
      (node (ref "J3") (pin "26") (pinfunction "26_26") (pintype "passive"))
    )
    (net (code "19") (name "ETH_CS") (class "Default")
      (node (ref "J35") (pin "7") (pinfunction "7_7") (pintype "passive"))
      (node (ref "R57") (pin "2") (pinfunction "2_2") (pintype "passive"))
    )
    (net (code "20") (name "ETH_MISO") (class "Default")
      (node (ref "J35") (pin "11") (pinfunction "11_11") (pintype "passive"))
      (node (ref "R51") (pin "2") (pinfunction "2_2") (pintype "passive"))
    )
    (net (code "21") (name "ETH_MOSI") (class "Default")
      (node (ref "J35") (pin "13") (pinfunction "13_13") (pintype "passive"))
      (node (ref "R19") (pin "2") (pinfunction "2_2") (pintype "passive"))
    )
    (net (code "22") (name "ETH_SCK") (class "Default")
      (node (ref "J35") (pin "9") (pinfunction "9_9") (pintype "passive"))
      (node (ref "R53") (pin "2") (pinfunction "2_2") (pintype "passive"))
    )
    (net (code "23") (name "GND") (class "Default")
      (node (ref "BUTTON") (pin "3") (pinfunction "P$3_3") (pintype "bidirectional"))
      (node (ref "BUTTON") (pin "4") (pinfunction "P$4_4") (pintype "bidirectional"))
      (node (ref "C1") (pin "1") (pinfunction "P$1_1") (pintype "passive"))
      (node (ref "C11") (pin "1") (pinfunction "P$1_1") (pintype "passive"))
      (node (ref "C12") (pin "1") (pinfunction "P$1_1") (pintype "passive"))
      (node (ref "C13") (pin "1") (pinfunction "P$1_1") (pintype "passive"))
      (node (ref "C14") (pin "1") (pinfunction "P$1_1") (pintype "passive"))
      (node (ref "C18") (pin "1") (pinfunction "P$1_1") (pintype "passive"))
      (node (ref "C19") (pin "1") (pinfunction "P$1_1") (pintype "passive"))
      (node (ref "C2") (pin "1") (pinfunction "P$1_1") (pintype "passive"))
      (node (ref "C20") (pin "1") (pinfunction "P$1_1") (pintype "passive"))
      (node (ref "C21") (pin "1") (pinfunction "P$1_1") (pintype "passive"))
      (node (ref "C22") (pin "1") (pinfunction "P$1_1") (pintype "passive"))
      (node (ref "C23") (pin "1") (pinfunction "P$1_1") (pintype "passive"))
      (node (ref "C24") (pin "1") (pinfunction "P$1_1") (pintype "passive"))
      (node (ref "C25") (pin "2") (pinfunction "2_2") (pintype "passive"))
      (node (ref "C26") (pin "1") (pinfunction "P$1_1") (pintype "passive"))
      (node (ref "C28") (pin "2") (pinfunction "2_2") (pintype "passive"))
      (node (ref "C29") (pin "P$2") (pinfunction "P$2_P$2") (pintype "passive"))
      (node (ref "C3") (pin "1") (pinfunction "P$1_1") (pintype "passive"))
      (node (ref "C30") (pin "1") (pinfunction "P$1_1") (pintype "passive"))
      (node (ref "C31") (pin "2") (pinfunction "2_2") (pintype "passive"))
      (node (ref "C33") (pin "1") (pinfunction "P$1_1") (pintype "passive"))
      (node (ref "C4") (pin "2") (pinfunction "2_2") (pintype "passive"))
      (node (ref "C47") (pin "2") (pinfunction "2_2") (pintype "passive"))
      (node (ref "C5") (pin "2") (pinfunction "2_2") (pintype "passive"))
      (node (ref "C54") (pin "2") (pinfunction "2_2") (pintype "passive"))
      (node (ref "C55") (pin "2") (pinfunction "2_2") (pintype "passive"))
      (node (ref "C56") (pin "2") (pinfunction "2_2") (pintype "passive"))
      (node (ref "C57") (pin "2") (pinfunction "2_2") (pintype "passive"))
      (node (ref "C58") (pin "2") (pinfunction "2_2") (pintype "passive"))
      (node (ref "C59") (pin "2") (pinfunction "2_2") (pintype "passive"))
      (node (ref "C6") (pin "1") (pinfunction "P$1_1") (pintype "passive"))
      (node (ref "C60") (pin "2") (pinfunction "2_2") (pintype "passive"))
      (node (ref "C62") (pin "2") (pinfunction "2_2") (pintype "passive"))
      (node (ref "C63") (pin "2") (pinfunction "2_2") (pintype "passive"))
      (node (ref "C64") (pin "2") (pinfunction "2_2") (pintype "passive"))
      (node (ref "C65") (pin "2") (pinfunction "2_2") (pintype "passive"))
      (node (ref "C7") (pin "1") (pinfunction "P$1_1") (pintype "passive"))
      (node (ref "D1") (pin "1") (pinfunction "1_1") (pintype "bidirectional"))
      (node (ref "D6") (pin "1") (pinfunction "1_1") (pintype "bidirectional"))
      (node (ref "DEBUG") (pin "3") (pinfunction "3_3") (pintype "bidirectional"))
      (node (ref "DEBUG") (pin "5") (pinfunction "5_5") (pintype "bidirectional"))
      (node (ref "DEBUG") (pin "9") (pinfunction "9_9") (pintype "bidirectional"))
      (node (ref "J1") (pin "1") (pinfunction "P$1_1") (pintype "bidirectional"))
      (node (ref "J1") (pin "15") (pinfunction "P$15_15") (pintype "bidirectional"))
      (node (ref "J1") (pin "21") (pinfunction "P$21_21") (pintype "bidirectional"))
      (node (ref "J1") (pin "3") (pinfunction "P$3_3") (pintype "bidirectional"))
      (node (ref "J1") (pin "5") (pinfunction "P$5_5") (pintype "bidirectional"))
      (node (ref "J1") (pin "56") (pinfunction "P$56_56") (pintype "bidirectional"))
      (node (ref "J1") (pin "7") (pinfunction "P$7_7") (pintype "bidirectional"))
      (node (ref "J1") (pin "76") (pinfunction "P$76_76") (pintype "power_in"))
      (node (ref "J1") (pin "77") (pinfunction "P$77_77") (pintype "power_in"))
      (node (ref "J1") (pin "9") (pinfunction "P$9_9") (pintype "bidirectional"))
      (node (ref "J10") (pin "4") (pinfunction "4_4") (pintype "bidirectional"))
      (node (ref "J11") (pin "4") (pinfunction "4_4") (pintype "bidirectional"))
      (node (ref "J14") (pin "2") (pinfunction "2_2") (pintype "passive"))
      (node (ref "J14") (pin "3") (pinfunction "3_3") (pintype "passive"))
      (node (ref "J15") (pin "1") (pinfunction "1_1") (pintype "passive"))
      (node (ref "J15") (pin "2") (pinfunction "2_2") (pintype "passive"))
      (node (ref "J2") (pin "2") (pinfunction "2_2") (pintype "passive"))
      (node (ref "J2") (pin "3") (pinfunction "3_3") (pintype "passive"))
      (node (ref "J3") (pin "1") (pinfunction "1_1") (pintype "passive"))
      (node (ref "J3") (pin "23") (pinfunction "23_23") (pintype "passive"))
      (node (ref "J3") (pin "3") (pinfunction "3_3") (pintype "passive"))
      (node (ref "J3") (pin "33") (pinfunction "33_33") (pintype "passive"))
      (node (ref "J3") (pin "42") (pinfunction "42_42") (pintype "passive"))
      (node (ref "J3") (pin "5") (pinfunction "5_5") (pintype "passive"))
      (node (ref "J3") (pin "7") (pinfunction "7_7") (pintype "passive"))
      (node (ref "J3") (pin "9") (pinfunction "9_9") (pintype "passive"))
      (node (ref "J35") (pin "23") (pinfunction "23_23") (pintype "passive"))
      (node (ref "J35") (pin "24") (pinfunction "24_24") (pintype "passive"))
      (node (ref "J4") (pin "1") (pinfunction "2_1") (pintype "passive"))
      (node (ref "J6") (pin "P$1") (pinfunction "GND_P$1") (pintype "bidirectional"))
      (node (ref "L1") (pin "1") (pinfunction "1_1") (pintype "bidirectional"))
      (node (ref "LED1") (pin "2") (pinfunction "K_2") (pintype "bidirectional"))
      (node (ref "LED2") (pin "2") (pinfunction "K_2") (pintype "bidirectional"))
      (node (ref "R10") (pin "1") (pinfunction "1_1") (pintype "passive"))
      (node (ref "R20") (pin "2") (pinfunction "2_2") (pintype "bidirectional"))
      (node (ref "R23") (pin "1") (pinfunction "1_1") (pintype "passive"))
      (node (ref "R33") (pin "2") (pinfunction "2_2") (pintype "passive"))
      (node (ref "R34") (pin "2") (pinfunction "2_2") (pintype "passive"))
      (node (ref "R37") (pin "2") (pinfunction "2_2") (pintype "bidirectional"))
      (node (ref "R38") (pin "1") (pinfunction "1_1") (pintype "bidirectional"))
      (node (ref "R55") (pin "2") (pinfunction "2_2") (pintype "passive"))
      (node (ref "RESET") (pin "1") (pinfunction "P$1_1") (pintype "bidirectional"))
      (node (ref "RESET") (pin "2") (pinfunction "P$2_2") (pintype "bidirectional"))
      (node (ref "RN1") (pin "1") (pinfunction "1_1") (pintype "passive"))
      (node (ref "RN1") (pin "2") (pinfunction "1_2") (pintype "passive"))
      (node (ref "RN1") (pin "3") (pinfunction "1_3") (pintype "passive"))
      (node (ref "RN1") (pin "4") (pinfunction "1_4") (pintype "passive"))
      (node (ref "RN2") (pin "1") (pinfunction "1_1") (pintype "passive"))
      (node (ref "S4") (pin "2") (pinfunction "2_2") (pintype "bidirectional"))
      (node (ref "S4") (pin "5") (pinfunction "5_5") (pintype "bidirectional"))
      (node (ref "U$2") (pin "P$1") (pinfunction "TP_P$1") (pintype "bidirectional"))
      (node (ref "U1") (pin "14") (pinfunction "AGND_14") (pintype "passive"))
      (node (ref "U1") (pin "16") (pinfunction "AGND_16") (pintype "passive"))
      (node (ref "U1") (pin "19") (pinfunction "AGND_19") (pintype "passive"))
      (node (ref "U1") (pin "23") (pinfunction "RSVD_23") (pintype "passive"))
      (node (ref "U1") (pin "29") (pinfunction "GND_29") (pintype "passive"))
      (node (ref "U1") (pin "3") (pinfunction "AGND_3") (pintype "passive"))
      (node (ref "U1") (pin "48") (pinfunction "AGND_48") (pintype "passive"))
      (node (ref "U1") (pin "9") (pinfunction "AGND_9") (pintype "passive"))
      (node (ref "U13") (pin "1") (pinfunction "CTG_1") (pintype "bidirectional"))
      (node (ref "U13") (pin "4") (pinfunction "GND_4") (pintype "bidirectional"))
      (node (ref "U13") (pin "6") (pinfunction "QST_6") (pintype "bidirectional"))
      (node (ref "U13") (pin "EP") (pinfunction "GND_EP") (pintype "bidirectional"))
      (node (ref "U14") (pin "17") (pinfunction "PGND_17") (pintype "passive"))
      (node (ref "U14") (pin "18") (pinfunction "PGND_18") (pintype "passive"))
      (node (ref "U14") (pin "PAD") (pinfunction "PAD_PAD") (pintype "power_in"))
      (node (ref "U14") (pin "PAD@1") (pinfunction "PAD_PAD@1") (pintype "power_in"))
      (node (ref "U14") (pin "PAD@2") (pinfunction "PAD_PAD@2") (pintype "power_in"))
      (node (ref "U14") (pin "PAD@3") (pinfunction "PAD_PAD@3") (pintype "power_in"))
      (node (ref "U14") (pin "PAD@4") (pinfunction "PAD_PAD@4") (pintype "power_in"))
      (node (ref "U14") (pin "PAD@5") (pinfunction "PAD_PAD@5") (pintype "power_in"))
      (node (ref "U14") (pin "PAD@6") (pinfunction "PAD_PAD@6") (pintype "power_in"))
      (node (ref "U14") (pin "PAD@7") (pinfunction "PAD_PAD@7") (pintype "power_in"))
      (node (ref "U14") (pin "PAD@8") (pinfunction "PAD_PAD@8") (pintype "power_in"))
      (node (ref "U14") (pin "PAD@9") (pinfunction "PAD_PAD@9") (pintype "power_in"))
      (node (ref "U2") (pin "2") (pinfunction "VSS_2") (pintype "power_in"))
      (node (ref "U3") (pin "2") (pinfunction "VSS_2") (pintype "power_in"))
      (node (ref "U3") (pin "5") (pinfunction "VSS_5") (pintype "power_in"))
      (node (ref "U3") (pin "P$1") (pinfunction "VSS_P$1") (pintype "power_in"))
      (node (ref "USB1") (pin "5") (pinfunction "GND3_5") (pintype "bidirectional"))
      (node (ref "USB1") (pin "6") (pinfunction "GND_6") (pintype "bidirectional"))
      (node (ref "USB1") (pin "7") (pinfunction "GND1_7") (pintype "bidirectional"))
      (node (ref "USB1") (pin "8") (pinfunction "GND4_8") (pintype "bidirectional"))
      (node (ref "USB1") (pin "9") (pinfunction "GND5_9") (pintype "bidirectional"))
      (node (ref "USB2") (pin "4") (pinfunction "ID_4") (pintype "bidirectional"))
      (node (ref "USB2") (pin "5") (pinfunction "GND3_5") (pintype "bidirectional"))
      (node (ref "USB2") (pin "6") (pinfunction "GND_6") (pintype "bidirectional"))
      (node (ref "USB2") (pin "7") (pinfunction "GND1_7") (pintype "bidirectional"))
      (node (ref "USB2") (pin "8") (pinfunction "GND4_8") (pintype "bidirectional"))
      (node (ref "USB2") (pin "9") (pinfunction "GND5_9") (pintype "bidirectional"))
      (node (ref "X1") (pin "2") (pinfunction "2_2") (pintype "passive"))
      (node (ref "X1") (pin "3") (pinfunction "2_3") (pintype "passive"))
      (node (ref "X1") (pin "4") (pinfunction "2_4") (pintype "passive"))
      (node (ref "X1") (pin "5") (pinfunction "2_5") (pintype "passive"))
      (node (ref "X3") (pin "2") (pinfunction "2_2") (pintype "passive"))
      (node (ref "X3") (pin "3") (pinfunction "2_3") (pintype "passive"))
      (node (ref "X3") (pin "4") (pinfunction "2_4") (pintype "passive"))
      (node (ref "X3") (pin "5") (pinfunction "2_5") (pintype "passive"))
      (node (ref "X4") (pin "6") (pinfunction "6-VSS_6") (pintype "bidirectional"))
      (node (ref "X4") (pin "GND1") (pinfunction "GND_GND1") (pintype "power_in"))
      (node (ref "X4") (pin "GND2") (pinfunction "GND1_GND2") (pintype "power_in"))
      (node (ref "Y1") (pin "2") (pinfunction "3_2") (pintype "passive"))
      (node (ref "Y1") (pin "4") (pinfunction "3_4") (pintype "passive"))
      (node (ref "Z1") (pin "1") (pinfunction "1_1") (pintype "passive"))
      (node (ref "Z2") (pin "1") (pinfunction "1_1") (pintype "passive"))
      (node (ref "Z3") (pin "1") (pinfunction "1_1") (pintype "passive"))
      (node (ref "Z4") (pin "1") (pinfunction "1_1") (pintype "passive"))
      (node (ref "Z5") (pin "1") (pinfunction "1_1") (pintype "passive"))
      (node (ref "Z6") (pin "1") (pinfunction "1_1") (pintype "passive"))
    )
    (net (code "24") (name "GPIO0") (class "Default")
      (node (ref "J1") (pin "62") (pinfunction "P$62_62") (pintype "bidirectional"))
      (node (ref "J3") (pin "48") (pinfunction "48_48") (pintype "passive"))
      (node (ref "J35") (pin "16") (pinfunction "16_16") (pintype "passive"))
    )
    (net (code "25") (name "GPIO1") (class "Default")
      (node (ref "J1") (pin "64") (pinfunction "P$64_64") (pintype "bidirectional"))
      (node (ref "J3") (pin "50") (pinfunction "50_50") (pintype "passive"))
    )
    (net (code "26") (name "GREEN") (class "Default")
      (node (ref "J1") (pin "63") (pinfunction "P$63_63") (pintype "bidirectional"))
      (node (ref "J3") (pin "47") (pinfunction "47_47") (pintype "passive"))
      (node (ref "R13") (pin "1") (pinfunction "1_1") (pintype "bidirectional"))
    )
    (net (code "27") (name "ILIM") (class "Default")
      (node (ref "R33") (pin "1") (pinfunction "1_1") (pintype "passive"))
      (node (ref "U14") (pin "10") (pinfunction "ILIM_10") (pintype "output"))
    )
    (net (code "28") (name "LINKLED") (class "Default")
      (node (ref "R47") (pin "2") (pinfunction "2_2") (pintype "passive"))
      (node (ref "U1") (pin "25") (pinfunction "LINKLED_25") (pintype "passive"))
    )
    (net (code "29") (name "MISO") (class "Default")
      (node (ref "J1") (pin "50") (pinfunction "P$50_50") (pintype "bidirectional"))
      (node (ref "J3") (pin "36") (pinfunction "36_36") (pintype "passive"))
      (node (ref "J35") (pin "12") (pinfunction "12_12") (pintype "passive"))
    )
    (net (code "30") (name "MODE") (class "Default")
      (node (ref "BUTTON") (pin "1") (pinfunction "P$1_1") (pintype "bidirectional"))
      (node (ref "BUTTON") (pin "2") (pinfunction "P$2_2") (pintype "bidirectional"))
      (node (ref "J1") (pin "32") (pinfunction "P$32_32") (pintype "bidirectional"))
      (node (ref "J3") (pin "18") (pinfunction "18_18") (pintype "passive"))
      (node (ref "Z3") (pin "2") (pinfunction "2_2") (pintype "passive"))
    )
    (net (code "31") (name "MOSI") (class "Default")
      (node (ref "J1") (pin "52") (pinfunction "P$52_52") (pintype "bidirectional"))
      (node (ref "J3") (pin "38") (pinfunction "38_38") (pintype "passive"))
      (node (ref "J35") (pin "14") (pinfunction "14_14") (pintype "passive"))
    )
    (net (code "32") (name "NC0") (class "Default")
      (node (ref "J1") (pin "14") (pinfunction "P$14_14") (pintype "bidirectional"))
      (node (ref "J3") (pin "10") (pinfunction "10_10") (pintype "passive"))
    )
    (net (code "33") (name "NC1") (class "Default")
      (node (ref "J1") (pin "18") (pinfunction "P$18_18") (pintype "bidirectional"))
      (node (ref "J3") (pin "12") (pinfunction "12_12") (pintype "passive"))
    )
    (net (code "34") (name "NC2") (class "Default")
      (node (ref "J1") (pin "58") (pinfunction "P$58_58") (pintype "bidirectional"))
      (node (ref "J3") (pin "44") (pinfunction "44_44") (pintype "passive"))
    )
    (net (code "35") (name "NC3") (class "Default")
      (node (ref "J1") (pin "60") (pinfunction "P$60_60") (pintype "bidirectional"))
      (node (ref "J3") (pin "46") (pinfunction "46_46") (pintype "passive"))
    )
    (net (code "36") (name "NC11") (class "Default")
      (node (ref "J1") (pin "51") (pinfunction "P$51_51") (pintype "bidirectional"))
      (node (ref "J3") (pin "35") (pinfunction "35_35") (pintype "passive"))
    )
    (net (code "37") (name "NC12") (class "Default")
      (node (ref "J1") (pin "53") (pinfunction "P$53_53") (pintype "bidirectional"))
      (node (ref "J3") (pin "37") (pinfunction "37_37") (pintype "passive"))
    )
    (net (code "38") (name "NC13") (class "Default")
      (node (ref "J1") (pin "55") (pinfunction "P$55_55") (pintype "bidirectional"))
      (node (ref "J3") (pin "39") (pinfunction "39_39") (pintype "passive"))
    )
    (net (code "39") (name "NC14") (class "Default")
      (node (ref "J1") (pin "57") (pinfunction "P$57_57") (pintype "bidirectional"))
      (node (ref "J3") (pin "41") (pinfunction "41_41") (pintype "bidirectional"))
    )
    (net (code "40") (name "NC15") (class "Default")
      (node (ref "J1") (pin "59") (pinfunction "P$59_59") (pintype "bidirectional"))
      (node (ref "J3") (pin "43") (pinfunction "43_43") (pintype "passive"))
    )
    (net (code "41") (name "NFC1") (class "Default")
      (node (ref "J1") (pin "17") (pinfunction "P$17_17") (pintype "bidirectional"))
      (node (ref "J3") (pin "11") (pinfunction "11_11") (pintype "passive"))
      (node (ref "NFC") (pin "2@1") (pinfunction "GND_2@1") (pintype "passive"))
      (node (ref "NFC") (pin "2@2") (pinfunction "GND_2@2") (pintype "passive"))
      (node (ref "R37") (pin "1") (pinfunction "1_1") (pintype "bidirectional"))
    )
    (net (code "42") (name "NFC2") (class "Default")
      (node (ref "J1") (pin "19") (pinfunction "P$19_19") (pintype "bidirectional"))
      (node (ref "J3") (pin "13") (pinfunction "13_13") (pintype "passive"))
      (node (ref "NFC") (pin "1") (pinfunction "1_1") (pintype "passive"))
      (node (ref "R38") (pin "2") (pinfunction "2_2") (pintype "bidirectional"))
    )
    (net (code "43") (name "Net-(C1-P$2)") (class "Default")
      (node (ref "C1") (pin "2") (pinfunction "P$2_2") (pintype "passive"))
      (node (ref "R32") (pin "1") (pinfunction "1_1") (pintype "passive"))
      (node (ref "RJ45") (pin "R4") (pinfunction "TCT_R4") (pintype "bidirectional"))
    )
    (net (code "44") (name "Net-(C11-P$2)") (class "Default")
      (node (ref "C11") (pin "2") (pinfunction "P$2_2") (pintype "passive"))
      (node (ref "R26") (pin "2") (pinfunction "2_2") (pintype "passive"))
      (node (ref "U1") (pin "30") (pinfunction "XI/CLKIN_30") (pintype "passive"))
      (node (ref "Y1") (pin "3") (pinfunction "2_3") (pintype "passive"))
    )
    (net (code "45") (name "Net-(C12-P$2)") (class "Default")
      (node (ref "C12") (pin "2") (pinfunction "P$2_2") (pintype "passive"))
      (node (ref "R50") (pin "2") (pinfunction "2_2") (pintype "bidirectional"))
      (node (ref "Y1") (pin "1") (pinfunction "1_1") (pintype "passive"))
    )
    (net (code "46") (name "Net-(C14-P$2)") (class "Default")
      (node (ref "C14") (pin "2") (pinfunction "P$2_2") (pintype "passive"))
      (node (ref "R40") (pin "1") (pinfunction "1_1") (pintype "passive"))
      (node (ref "R41") (pin "1") (pinfunction "1_1") (pintype "passive"))
      (node (ref "RJ45") (pin "R3") (pinfunction "RCT_R3") (pintype "bidirectional"))
    )
    (net (code "47") (name "Net-(C15-P$2)") (class "Default")
      (node (ref "C15") (pin "2") (pinfunction "P$2_2") (pintype "passive"))
      (node (ref "RJ45") (pin "R2") (pinfunction "RD+_R2") (pintype "bidirectional"))
    )
    (net (code "48") (name "Net-(C16-P$2)") (class "Default")
      (node (ref "C16") (pin "2") (pinfunction "P$2_2") (pintype "passive"))
      (node (ref "RJ45") (pin "R1") (pinfunction "RD-_R1") (pintype "bidirectional"))
    )
    (net (code "49") (name "Net-(C26-P$2)") (class "Default")
      (node (ref "C26") (pin "2") (pinfunction "P$2_2") (pintype "passive"))
      (node (ref "U1") (pin "22") (pinfunction "1V2O_22") (pintype "passive"))
    )
    (net (code "50") (name "Net-(D5-PadA)") (class "Default")
      (node (ref "D5") (pin "A") (pinfunction "A_A") (pintype "passive"))
      (node (ref "R44") (pin "1") (pinfunction "1_1") (pintype "passive"))
    )
    (net (code "51") (name "Net-(D7-PadANODE)") (class "Default")
      (node (ref "D7") (pin "ANODE") (pinfunction "ANODE_ANODE") (pintype "bidirectional"))
      (node (ref "J2") (pin "1") (pinfunction "1_1") (pintype "passive"))
    )
    (net (code "52") (name "Net-(D8-P$2)") (class "Default")
      (node (ref "D8") (pin "2") (pinfunction "P$2_2") (pintype "bidirectional"))
      (node (ref "DEBUG") (pin "1") (pinfunction "1_1") (pintype "bidirectional"))
      (node (ref "U$1") (pin "P$1") (pinfunction "TP_P$1") (pintype "bidirectional"))
    )
    (net (code "53") (name "Net-(F1-1)") (class "Default")
      (node (ref "D6") (pin "2") (pinfunction "2_2") (pintype "bidirectional"))
      (node (ref "F1") (pin "P$1") (pinfunction "1_P$1") (pintype "bidirectional"))
      (node (ref "USB1") (pin "1") (pinfunction "VBUS_1") (pintype "bidirectional"))
    )
    (net (code "54") (name "Net-(F2-1)") (class "Default")
      (node (ref "D1") (pin "2") (pinfunction "2_2") (pintype "bidirectional"))
      (node (ref "F2") (pin "P$1") (pinfunction "1_P$1") (pintype "bidirectional"))
      (node (ref "USB2") (pin "1") (pinfunction "VBUS_1") (pintype "bidirectional"))
    )
    (net (code "55") (name "Net-(J4-1)") (class "Default")
      (node (ref "J4") (pin "2") (pinfunction "1_2") (pintype "passive"))
      (node (ref "Q2") (pin "3") (pinfunction "3_3") (pintype "bidirectional"))
    )
    (net (code "56") (name "Net-(J7-Pad1)") (class "Default")
      (node (ref "J7") (pin "1") (pinfunction "1_1") (pintype "passive"))
      (node (ref "R44") (pin "2") (pinfunction "2_2") (pintype "passive"))
    )
    (net (code "57") (name "Net-(L2-1)") (class "Default")
      (node (ref "L2") (pin "P$1") (pinfunction "1_P$1") (pintype "passive"))
      (node (ref "U3") (pin "1") (pinfunction "LX_1") (pintype "bidirectional"))
    )
    (net (code "58") (name "Net-(LED1-A)") (class "Default")
      (node (ref "LED1") (pin "1") (pinfunction "A_1") (pintype "bidirectional"))
      (node (ref "R14") (pin "2") (pinfunction "2_2") (pintype "bidirectional"))
    )
    (net (code "59") (name "Net-(LED2-A)") (class "Default")
      (node (ref "LED2") (pin "1") (pinfunction "A_1") (pintype "bidirectional"))
      (node (ref "R52") (pin "2") (pinfunction "2_2") (pintype "bidirectional"))
    )
    (net (code "60") (name "Net-(Q2-Pad1)") (class "Default")
      (node (ref "Q2") (pin "1") (pinfunction "1_1") (pintype "bidirectional"))
      (node (ref "Q3") (pin "1") (pinfunction "1_1") (pintype "bidirectional"))
      (node (ref "R7") (pin "1") (pinfunction "1_1") (pintype "bidirectional"))
      (node (ref "R8") (pin "1") (pinfunction "1_1") (pintype "bidirectional"))
    )
    (net (code "61") (name "Net-(Q2-Pad2)") (class "Default")
      (node (ref "Q2") (pin "2") (pinfunction "2_2") (pintype "bidirectional"))
      (node (ref "Q3") (pin "2") (pinfunction "2_2") (pintype "bidirectional"))
      (node (ref "R7") (pin "2") (pinfunction "2_2") (pintype "bidirectional"))
    )
    (net (code "62") (name "Net-(R8-Pad2)") (class "Default")
      (node (ref "R8") (pin "2") (pinfunction "2_2") (pintype "bidirectional"))
      (node (ref "S4") (pin "3") (pinfunction "3_3") (pintype "bidirectional"))
      (node (ref "S4") (pin "6") (pinfunction "6_6") (pintype "bidirectional"))
    )
    (net (code "63") (name "Net-(R55-Pad1)") (class "Default")
      (node (ref "R55") (pin "1") (pinfunction "1_1") (pintype "passive"))
      (node (ref "S1") (pin "3") (pinfunction "3_3") (pintype "bidirectional"))
      (node (ref "S1") (pin "6") (pinfunction "6_6") (pintype "bidirectional"))
    )
    (net (code "64") (name "Net-(RGB-2)") (class "Default")
      (node (ref "R15") (pin "2") (pinfunction "2_2") (pintype "bidirectional"))
      (node (ref "RGB") (pin "BLUE") (pinfunction "2_BLUE") (pintype "passive"))
    )
    (net (code "65") (name "Net-(RGB-3)") (class "Default")
      (node (ref "R13") (pin "2") (pinfunction "2_2") (pintype "bidirectional"))
      (node (ref "RGB") (pin "GREEN") (pinfunction "3_GREEN") (pintype "passive"))
    )
    (net (code "66") (name "Net-(RGB-4)") (class "Default")
      (node (ref "R12") (pin "2") (pinfunction "2_2") (pintype "bidirectional"))
      (node (ref "RGB") (pin "RED") (pinfunction "4_RED") (pintype "passive"))
    )
    (net (code "67") (name "Net-(RJ45-L2Y-)") (class "Default")
      (node (ref "R48") (pin "1") (pinfunction "1_1") (pintype "passive"))
      (node (ref "RJ45") (pin "12") (pinfunction "L2Y-_12") (pintype "bidirectional"))
    )
    (net (code "68") (name "Net-(RJ45-L4G-)") (class "Default")
      (node (ref "R47") (pin "1") (pinfunction "1_1") (pintype "passive"))
      (node (ref "RJ45") (pin "14") (pinfunction "L4G-_14") (pintype "bidirectional"))
    )
    (net (code "69") (name "Net-(RN1A-2)") (class "Default")
      (node (ref "RN1") (pin "8") (pinfunction "2_8") (pintype "passive"))
      (node (ref "U1") (pin "38") (pinfunction "RSVD_38") (pintype "passive"))
    )
    (net (code "70") (name "Net-(RN1B-2)") (class "Default")
      (node (ref "RN1") (pin "7") (pinfunction "2_7") (pintype "passive"))
      (node (ref "U1") (pin "39") (pinfunction "RSVD_39") (pintype "passive"))
    )
    (net (code "71") (name "Net-(RN1C-2)") (class "Default")
      (node (ref "RN1") (pin "6") (pinfunction "2_6") (pintype "passive"))
      (node (ref "U1") (pin "40") (pinfunction "RSVD_40") (pintype "passive"))
    )
    (net (code "72") (name "Net-(RN1D-2)") (class "Default")
      (node (ref "RN1") (pin "5") (pinfunction "2_5") (pintype "passive"))
      (node (ref "U1") (pin "41") (pinfunction "RSVD_41") (pintype "passive"))
    )
    (net (code "73") (name "Net-(RN2A-2)") (class "Default")
      (node (ref "RN2") (pin "8") (pinfunction "2_8") (pintype "passive"))
      (node (ref "U1") (pin "42") (pinfunction "RSVD_42") (pintype "passive"))
    )
    (net (code "74") (name "Net-(RN2B-2)") (class "Default")
      (node (ref "RN2") (pin "7") (pinfunction "2_7") (pintype "passive"))
      (node (ref "U1") (pin "43") (pinfunction "PMODE2_43") (pintype "passive"))
    )
    (net (code "75") (name "Net-(RN2C-2)") (class "Default")
      (node (ref "RN2") (pin "6") (pinfunction "2_6") (pintype "passive"))
      (node (ref "U1") (pin "44") (pinfunction "PMODE1_44") (pintype "passive"))
    )
    (net (code "76") (name "Net-(RN2D-2)") (class "Default")
      (node (ref "RN2") (pin "5") (pinfunction "2_5") (pintype "passive"))
      (node (ref "U1") (pin "45") (pinfunction "PMODE0_45") (pintype "passive"))
    )
    (net (code "77") (name "Net-(U1-EXRES1)") (class "Default")
      (node (ref "R23") (pin "2") (pinfunction "2_2") (pintype "passive"))
      (node (ref "U1") (pin "10") (pinfunction "EXRES1_10") (pintype "passive"))
    )
    (net (code "78") (name "Net-(U1-MISO)") (class "Default")
      (node (ref "R51") (pin "1") (pinfunction "1_1") (pintype "passive"))
      (node (ref "R59") (pin "1") (pinfunction "1_1") (pintype "passive"))
      (node (ref "U1") (pin "34") (pinfunction "MISO_34") (pintype "passive"))
    )
    (net (code "79") (name "Net-(U1-MOSI)") (class "Default")
      (node (ref "R19") (pin "1") (pinfunction "1_1") (pintype "passive"))
      (node (ref "R60") (pin "1") (pinfunction "1_1") (pintype "passive"))
      (node (ref "U1") (pin "35") (pinfunction "MOSI_35") (pintype "passive"))
    )
    (net (code "80") (name "Net-(U1-RXN)") (class "Default")
      (node (ref "R46") (pin "2") (pinfunction "2_2") (pintype "passive"))
      (node (ref "U1") (pin "5") (pinfunction "RXN_5") (pintype "passive"))
    )
    (net (code "81") (name "Net-(U1-RXP)") (class "Default")
      (node (ref "R45") (pin "2") (pinfunction "2_2") (pintype "passive"))
      (node (ref "U1") (pin "6") (pinfunction "RXP_6") (pintype "passive"))
    )
    (net (code "82") (name "Net-(U1-SCLK)") (class "Default")
      (node (ref "R53") (pin "1") (pinfunction "1_1") (pintype "passive"))
      (node (ref "U1") (pin "33") (pinfunction "SCLK_33") (pintype "passive"))
    )
    (net (code "83") (name "Net-(U1-SCS_N)") (class "Default")
      (node (ref "R24") (pin "1") (pinfunction "1_1") (pintype "passive"))
      (node (ref "R57") (pin "1") (pinfunction "1_1") (pintype "passive"))
      (node (ref "U1") (pin "32") (pinfunction "SCS_N_32") (pintype "passive"))
    )
    (net (code "84") (name "Net-(U1-TOCAP)") (class "Default")
      (node (ref "C31") (pin "1") (pinfunction "1_1") (pintype "passive"))
      (node (ref "U1") (pin "20") (pinfunction "TOCAP_20") (pintype "passive"))
    )
    (net (code "85") (name "Net-(U1-TXN)") (class "Default")
      (node (ref "R43") (pin "2") (pinfunction "2_2") (pintype "passive"))
      (node (ref "U1") (pin "1") (pinfunction "TXN_1") (pintype "passive"))
    )
    (net (code "86") (name "Net-(U1-TXP)") (class "Default")
      (node (ref "R42") (pin "2") (pinfunction "2_2") (pintype "passive"))
      (node (ref "U1") (pin "2") (pinfunction "TXP_2") (pintype "passive"))
    )
    (net (code "87") (name "Net-(U1-XO)") (class "Default")
      (node (ref "R26") (pin "1") (pinfunction "1_1") (pintype "passive"))
      (node (ref "R50") (pin "1") (pinfunction "1_1") (pintype "bidirectional"))
      (node (ref "U1") (pin "31") (pinfunction "XO_31") (pintype "passive"))
    )
    (net (code "88") (name "Net-(U3-CE)") (class "Default")
      (node (ref "R11") (pin "2") (pinfunction "2_2") (pintype "passive"))
      (node (ref "U3") (pin "4") (pinfunction "CE_4") (pintype "bidirectional"))
    )
    (net (code "89") (name "Net-(U13-CELL)") (class "Default")
      (node (ref "C55") (pin "1") (pinfunction "1_1") (pintype "passive"))
      (node (ref "R54") (pin "2") (pinfunction "2_2") (pintype "passive"))
      (node (ref "U13") (pin "2") (pinfunction "CELL_2") (pintype "bidirectional"))
    )
    (net (code "90") (name "Net-(U13-VDD)") (class "Default")
      (node (ref "C54") (pin "1") (pinfunction "1_1") (pintype "passive"))
      (node (ref "R16") (pin "1") (pinfunction "1_1") (pintype "passive"))
      (node (ref "U13") (pin "3") (pinfunction "VDD_3") (pintype "bidirectional"))
    )
    (net (code "91") (name "Net-(USB1-D+)") (class "Default")
      (node (ref "R5") (pin "2") (pinfunction "2_2") (pintype "bidirectional"))
      (node (ref "USB1") (pin "3") (pinfunction "D+_3") (pintype "bidirectional"))
      (node (ref "Z1") (pin "2") (pinfunction "2_2") (pintype "passive"))
    )
    (net (code "92") (name "Net-(USB1-D-)") (class "Default")
      (node (ref "R6") (pin "2") (pinfunction "2_2") (pintype "bidirectional"))
      (node (ref "USB1") (pin "2") (pinfunction "D-_2") (pintype "bidirectional"))
      (node (ref "Z2") (pin "2") (pinfunction "2_2") (pintype "passive"))
    )
    (net (code "93") (name "Net-(USB1-ID)") (class "Default")
      (node (ref "R20") (pin "1") (pinfunction "1_1") (pintype "bidirectional"))
      (node (ref "R21") (pin "1") (pinfunction "1_1") (pintype "bidirectional"))
      (node (ref "R22") (pin "1") (pinfunction "1_1") (pintype "bidirectional"))
      (node (ref "USB1") (pin "4") (pinfunction "ID_4") (pintype "bidirectional"))
    )
    (net (code "94") (name "OTG") (class "Default")
      (node (ref "R3") (pin "2") (pinfunction "2_2") (pintype "passive"))
      (node (ref "U14") (pin "8") (pinfunction "OTG_8") (pintype "bidirectional"))
    )
    (net (code "95") (name "PMIC_SYS") (class "Default")
      (node (ref "C47") (pin "1") (pinfunction "1_1") (pintype "passive"))
      (node (ref "C58") (pin "1") (pinfunction "1_1") (pintype "passive"))
      (node (ref "C59") (pin "1") (pinfunction "1_1") (pintype "passive"))
      (node (ref "J7") (pin "2") (pinfunction "2_2") (pintype "passive"))
      (node (ref "L7") (pin "P$2") (pinfunction "2_P$2") (pintype "passive"))
      (node (ref "R4") (pin "2") (pinfunction "2_2") (pintype "bidirectional"))
      (node (ref "U14") (pin "15") (pinfunction "SYS_15") (pintype "power_in"))
      (node (ref "U14") (pin "16") (pinfunction "SYS_16") (pintype "power_in"))
      (node (ref "U2") (pin "5") (pinfunction "VIN_5") (pintype "power_in"))
    )
    (net (code "96") (name "PMID") (class "Default")
      (node (ref "C56") (pin "1") (pinfunction "1_1") (pintype "passive"))
      (node (ref "C62") (pin "1") (pinfunction "1_1") (pintype "passive"))
      (node (ref "U14") (pin "23") (pinfunction "PMID_23") (pintype "passive"))
    )
    (net (code "97") (name "PWM0") (class "Default")
      (node (ref "J1") (pin "66") (pinfunction "P$66_66") (pintype "bidirectional"))
      (node (ref "J12") (pin "1") (pinfunction "1_1") (pintype "passive"))
      (node (ref "J3") (pin "52") (pinfunction "52_52") (pintype "passive"))
    )
    (net (code "98") (name "PWM1") (class "Default")
      (node (ref "J1") (pin "68") (pinfunction "P$68_68") (pintype "bidirectional"))
      (node (ref "J12") (pin "7") (pinfunction "7_7") (pintype "passive"))
      (node (ref "J3") (pin "54") (pinfunction "54_54") (pintype "passive"))
    )
    (net (code "99") (name "PWM2") (class "Default")
      (node (ref "J1") (pin "70") (pinfunction "P$70_70") (pintype "bidirectional"))
      (node (ref "J12") (pin "9") (pinfunction "9_9") (pintype "passive"))
      (node (ref "J3") (pin "56") (pinfunction "56_56") (pintype "passive"))
    )
    (net (code "100") (name "PWM3") (class "Default")
      (node (ref "J1") (pin "72") (pinfunction "P$72_72") (pintype "bidirectional"))
      (node (ref "J12") (pin "11") (pinfunction "11_11") (pintype "passive"))
      (node (ref "J3") (pin "58") (pinfunction "58_58") (pintype "passive"))
    )
    (net (code "101") (name "RED") (class "Default")
      (node (ref "J1") (pin "61") (pinfunction "P$61_61") (pintype "bidirectional"))
      (node (ref "J3") (pin "45") (pinfunction "45_45") (pintype "passive"))
      (node (ref "R12") (pin "1") (pinfunction "1_1") (pintype "bidirectional"))
    )
    (net (code "102") (name "REGN") (class "Default")
      (node (ref "C65") (pin "1") (pinfunction "1_1") (pintype "passive"))
      (node (ref "R35") (pin "1") (pinfunction "1_1") (pintype "passive"))
      (node (ref "U14") (pin "22") (pinfunction "REGN_22") (pintype "bidirectional"))
    )
    (net (code "103") (name "RTS") (class "Default")
      (node (ref "J1") (pin "42") (pinfunction "P$42_42") (pintype "bidirectional"))
      (node (ref "J12") (pin "3") (pinfunction "3_3") (pintype "passive"))
      (node (ref "J3") (pin "28") (pinfunction "28_28") (pintype "passive"))
    )
    (net (code "104") (name "RX") (class "Default")
      (node (ref "J1") (pin "38") (pinfunction "P$38_38") (pintype "bidirectional"))
      (node (ref "J3") (pin "24") (pinfunction "24_24") (pintype "passive"))
    )
    (net (code "105") (name "RX_N") (class "Default")
      (node (ref "C16") (pin "1") (pinfunction "P$1_1") (pintype "passive"))
      (node (ref "R41") (pin "2") (pinfunction "2_2") (pintype "passive"))
      (node (ref "R46") (pin "1") (pinfunction "1_1") (pintype "passive"))
    )
    (net (code "106") (name "RX_P") (class "Default")
      (node (ref "C15") (pin "1") (pinfunction "P$1_1") (pintype "passive"))
      (node (ref "R40") (pin "2") (pinfunction "2_2") (pintype "passive"))
      (node (ref "R45") (pin "1") (pinfunction "1_1") (pintype "passive"))
    )
    (net (code "107") (name "SCK") (class "Default")
      (node (ref "J1") (pin "54") (pinfunction "P$54_54") (pintype "bidirectional"))
      (node (ref "J3") (pin "40") (pinfunction "40_40") (pintype "passive"))
      (node (ref "J35") (pin "10") (pinfunction "10_10") (pintype "passive"))
    )
    (net (code "108") (name "SCL") (class "Default")
      (node (ref "J1") (pin "20") (pinfunction "P$20_20") (pintype "bidirectional"))
      (node (ref "J10") (pin "1") (pinfunction "1_1") (pintype "bidirectional"))
      (node (ref "J3") (pin "14") (pinfunction "14_14") (pintype "passive"))
      (node (ref "J35") (pin "22") (pinfunction "22_22") (pintype "passive"))
    )
    (net (code "109") (name "SCL-P") (class "Default")
      (node (ref "J35") (pin "21") (pinfunction "21_21") (pintype "passive"))
      (node (ref "R30") (pin "2") (pinfunction "2_2") (pintype "passive"))
      (node (ref "U13") (pin "7") (pinfunction "SCL_7") (pintype "bidirectional"))
      (node (ref "U14") (pin "5") (pinfunction "SCL_5") (pintype "output"))
    )
    (net (code "110") (name "SDA") (class "Default")
      (node (ref "J1") (pin "22") (pinfunction "P$22_22") (pintype "bidirectional"))
      (node (ref "J10") (pin "2") (pinfunction "2_2") (pintype "bidirectional"))
      (node (ref "J3") (pin "16") (pinfunction "16_16") (pintype "passive"))
      (node (ref "J35") (pin "20") (pinfunction "20_20") (pintype "passive"))
    )
    (net (code "111") (name "SDA-P") (class "Default")
      (node (ref "J35") (pin "19") (pinfunction "19_19") (pintype "passive"))
      (node (ref "R36") (pin "2") (pinfunction "2_2") (pintype "passive"))
      (node (ref "U13") (pin "8") (pinfunction "SDA_8") (pintype "bidirectional"))
      (node (ref "U14") (pin "6") (pinfunction "SDA_6") (pintype "bidirectional"))
    )
    (net (code "112") (name "SD_CLK1") (class "Default")
      (node (ref "J12") (pin "4") (pinfunction "4_4") (pintype "passive"))
      (node (ref "R27") (pin "2") (pinfunction "2_2") (pintype "bidirectional"))
      (node (ref "X4") (pin "5") (pinfunction "5-CLK_5") (pintype "bidirectional"))
    )
    (net (code "113") (name "SD_CS1") (class "Default")
      (node (ref "J12") (pin "8") (pinfunction "8_8") (pintype "passive"))
      (node (ref "R28") (pin "2") (pinfunction "2_2") (pintype "bidirectional"))
      (node (ref "X4") (pin "2") (pinfunction "2-CD/DAT3_2") (pintype "bidirectional"))
    )
    (net (code "114") (name "SD_DECT") (class "Default")
      (node (ref "J12") (pin "10") (pinfunction "10_10") (pintype "passive"))
      (node (ref "R9") (pin "1") (pinfunction "1_1") (pintype "bidirectional"))
      (node (ref "X4") (pin "GND3") (pinfunction "GND2_GND3") (pintype "power_in"))
      (node (ref "X4") (pin "GND4") (pinfunction "GND3_GND4") (pintype "power_in"))
    )
    (net (code "115") (name "SD_MISO1") (class "Default")
      (node (ref "J12") (pin "2") (pinfunction "2_2") (pintype "passive"))
      (node (ref "X4") (pin "7") (pinfunction "7-DAT0_7") (pintype "bidirectional"))
    )
    (net (code "116") (name "SD_MOSI1") (class "Default")
      (node (ref "J12") (pin "6") (pinfunction "6_6") (pintype "passive"))
      (node (ref "R29") (pin "2") (pinfunction "2_2") (pintype "bidirectional"))
      (node (ref "X4") (pin "3") (pinfunction "3-CMO_3") (pintype "bidirectional"))
    )
    (net (code "117") (name "SOM5") (class "Default")
      (node (ref "J1") (pin "67") (pinfunction "P$67_67") (pintype "bidirectional"))
      (node (ref "J3") (pin "51") (pinfunction "51_51") (pintype "passive"))
    )
    (net (code "118") (name "SOM6") (class "Default")
      (node (ref "J1") (pin "69") (pinfunction "P$69_69") (pintype "bidirectional"))
      (node (ref "J3") (pin "53") (pinfunction "53_53") (pintype "passive"))
    )
    (net (code "119") (name "SOM7") (class "Default")
      (node (ref "J1") (pin "71") (pinfunction "P$71_71") (pintype "bidirectional"))
      (node (ref "J3") (pin "55") (pinfunction "55_55") (pintype "passive"))
    )
    (net (code "120") (name "SOM8") (class "Default")
      (node (ref "J1") (pin "73") (pinfunction "P$73_73") (pintype "bidirectional"))
      (node (ref "J3") (pin "57") (pinfunction "57_57") (pintype "passive"))
    )
    (net (code "121") (name "SOM9") (class "Default")
      (node (ref "J1") (pin "75") (pinfunction "P$75_75") (pintype "bidirectional"))
      (node (ref "J3") (pin "59") (pinfunction "59_59") (pintype "passive"))
    )
    (net (code "122") (name "STAT") (class "Default")
      (node (ref "D5") (pin "C") (pinfunction "C_C") (pintype "passive"))
      (node (ref "U14") (pin "4") (pinfunction "STAT_4") (pintype "bidirectional"))
    )
    (net (code "123") (name "SW1") (class "Default")
      (node (ref "C17") (pin "2") (pinfunction "2_2") (pintype "passive"))
      (node (ref "L7") (pin "P$1") (pinfunction "1_P$1") (pintype "passive"))
      (node (ref "U14") (pin "19") (pinfunction "SW_19") (pintype "power_in"))
      (node (ref "U14") (pin "20") (pinfunction "SW_20") (pintype "power_in"))
    )
    (net (code "124") (name "SWDCLK") (class "Default")
      (node (ref "DEBUG") (pin "4") (pinfunction "4_4") (pintype "bidirectional"))
      (node (ref "P2") (pin "P$2") (pinfunction "TP_P$2") (pintype "bidirectional"))
      (node (ref "U$10") (pin "P$1") (pinfunction "TP_P$1") (pintype "bidirectional"))
    )
    (net (code "125") (name "SWDIO") (class "Default")
      (node (ref "DEBUG") (pin "2") (pinfunction "2_2") (pintype "bidirectional"))
      (node (ref "P1") (pin "P$2") (pinfunction "TP_P$2") (pintype "bidirectional"))
      (node (ref "U$9") (pin "P$1") (pinfunction "TP_P$1") (pintype "bidirectional"))
    )
    (net (code "126") (name "SWO") (class "Default")
      (node (ref "DEBUG") (pin "6") (pinfunction "6_6") (pintype "bidirectional"))
      (node (ref "P3") (pin "P$2") (pinfunction "TP_P$2") (pintype "bidirectional"))
      (node (ref "U$11") (pin "P$1") (pinfunction "TP_P$1") (pintype "bidirectional"))
    )
    (net (code "127") (name "SYS_PWR_EN") (class "Default")
      (node (ref "R4") (pin "1") (pinfunction "1_1") (pintype "bidirectional"))
      (node (ref "S1") (pin "2") (pinfunction "2_2") (pintype "bidirectional"))
      (node (ref "S1") (pin "5") (pinfunction "5_5") (pintype "bidirectional"))
      (node (ref "U2") (pin "4") (pinfunction "CE_4") (pintype "bidirectional"))
    )
    (net (code "128") (name "TS") (class "Default")
      (node (ref "R34") (pin "1") (pinfunction "1_1") (pintype "passive"))
      (node (ref "R35") (pin "2") (pinfunction "2_2") (pintype "passive"))
      (node (ref "U14") (pin "11") (pinfunction "TS_11") (pintype "bidirectional"))
      (node (ref "U14") (pin "12") (pinfunction "~{QON}_12") (pintype "bidirectional"))
    )
    (net (code "129") (name "TX") (class "Default")
      (node (ref "J1") (pin "36") (pinfunction "P$36_36") (pintype "bidirectional"))
      (node (ref "J3") (pin "22") (pinfunction "22_22") (pintype "passive"))
    )
    (net (code "130") (name "TX_N") (class "Default")
      (node (ref "R31") (pin "1") (pinfunction "1_1") (pintype "passive"))
      (node (ref "R43") (pin "1") (pinfunction "1_1") (pintype "passive"))
      (node (ref "RJ45") (pin "R5") (pinfunction "TD-_R5") (pintype "bidirectional"))
    )
    (net (code "131") (name "TX_P") (class "Default")
      (node (ref "R39") (pin "1") (pinfunction "1_1") (pintype "passive"))
      (node (ref "R42") (pin "1") (pinfunction "1_1") (pintype "passive"))
      (node (ref "RJ45") (pin "R6") (pinfunction "TD+_R6") (pintype "bidirectional"))
    )
    (net (code "132") (name "U-VBUS") (class "Default")
      (node (ref "F2") (pin "P$2") (pinfunction "2_P$2") (pintype "bidirectional"))
      (node (ref "J35") (pin "5") (pinfunction "5_5") (pintype "passive"))
    )
    (net (code "133") (name "UB_N") (class "Default")
      (node (ref "J1") (pin "46") (pinfunction "P$46_46") (pintype "bidirectional"))
      (node (ref "R18") (pin "2") (pinfunction "2_2") (pintype "bidirectional"))
    )
    (net (code "134") (name "UB_P") (class "Default")
      (node (ref "J1") (pin "44") (pinfunction "P$44_44") (pintype "bidirectional"))
      (node (ref "R17") (pin "2") (pinfunction "2_2") (pintype "bidirectional"))
    )
    (net (code "135") (name "UB_USB_N") (class "Default")
      (node (ref "J35") (pin "2") (pinfunction "2_2") (pintype "passive"))
      (node (ref "R18") (pin "1") (pinfunction "1_1") (pintype "bidirectional"))
    )
    (net (code "136") (name "UB_USB_P") (class "Default")
      (node (ref "J35") (pin "4") (pinfunction "4_4") (pintype "passive"))
      (node (ref "R17") (pin "1") (pinfunction "1_1") (pintype "bidirectional"))
    )
    (net (code "137") (name "USBD_N") (class "Default")
      (node (ref "J1") (pin "13") (pinfunction "P$13_13") (pintype "bidirectional"))
      (node (ref "R6") (pin "1") (pinfunction "1_1") (pintype "bidirectional"))
      (node (ref "U14") (pin "3") (pinfunction "~{PG}_3") (pintype "output"))
    )
    (net (code "138") (name "USBD_P") (class "Default")
      (node (ref "J1") (pin "11") (pinfunction "P$11_11") (pintype "bidirectional"))
      (node (ref "R5") (pin "1") (pinfunction "1_1") (pintype "bidirectional"))
      (node (ref "U14") (pin "2") (pinfunction "PSEL_2") (pintype "output"))
    )
    (net (code "139") (name "USBID") (class "Default")
      (node (ref "R21") (pin "2") (pinfunction "2_2") (pintype "bidirectional"))
    )
    (net (code "140") (name "USB_DET") (class "Default")
      (node (ref "J1") (pin "74") (pinfunction "P$74_74") (pintype "bidirectional"))
      (node (ref "J35") (pin "6") (pinfunction "6_6") (pintype "passive"))
    )
    (net (code "141") (name "USER_D7") (class "Default")
      (node (ref "J12") (pin "12") (pinfunction "12_12") (pintype "passive"))
      (node (ref "R52") (pin "1") (pinfunction "1_1") (pintype "bidirectional"))
    )
    (net (code "142") (name "UVCC") (class "Default")
      (node (ref "J1") (pin "2") (pinfunction "P$2_2") (pintype "bidirectional"))
      (node (ref "J1") (pin "4") (pinfunction "P$4_4") (pintype "bidirectional"))
      (node (ref "J1") (pin "6") (pinfunction "P$6_6") (pintype "bidirectional"))
      (node (ref "J1") (pin "8") (pinfunction "P$8_8") (pintype "bidirectional"))
      (node (ref "J5") (pin "1") (pinfunction "1_1") (pintype "passive"))
    )
    (net (code "143") (name "U_N") (class "Default")
      (node (ref "J35") (pin "1") (pinfunction "1_1") (pintype "passive"))
      (node (ref "USB2") (pin "2") (pinfunction "D-_2") (pintype "bidirectional"))
      (node (ref "Z6") (pin "2") (pinfunction "2_2") (pintype "passive"))
    )
    (net (code "144") (name "U_P") (class "Default")
      (node (ref "J35") (pin "3") (pinfunction "3_3") (pintype "passive"))
      (node (ref "USB2") (pin "3") (pinfunction "D+_3") (pintype "bidirectional"))
      (node (ref "Z5") (pin "2") (pinfunction "2_2") (pintype "passive"))
    )
    (net (code "145") (name "V+") (class "Default")
      (node (ref "J16") (pin "2") (pinfunction "2_2") (pintype "passive"))
      (node (ref "RJ45") (pin "R9") (pinfunction "V+_R9") (pintype "bidirectional"))
    )
    (net (code "146") (name "V-") (class "Default")
      (node (ref "J16") (pin "1") (pinfunction "1_1") (pintype "passive"))
      (node (ref "RJ45") (pin "R10") (pinfunction "V-_R10") (pintype "bidirectional"))
    )
    (net (code "147") (name "VBAT") (class "Default")
      (node (ref "C63") (pin "1") (pinfunction "1_1") (pintype "passive"))
      (node (ref "Q3") (pin "3") (pinfunction "3_3") (pintype "bidirectional"))
      (node (ref "R54") (pin "1") (pinfunction "1_1") (pintype "passive"))
      (node (ref "U14") (pin "13") (pinfunction "BAT_13") (pintype "passive"))
      (node (ref "U14") (pin "14") (pinfunction "BAT_14") (pintype "power_in"))
    )
    (net (code "148") (name "VCC") (class "Default")
      (node (ref "C4") (pin "1") (pinfunction "1_1") (pintype "passive"))
      (node (ref "C6") (pin "2") (pinfunction "P$2_2") (pintype "passive"))
      (node (ref "J3") (pin "2") (pinfunction "2_2") (pintype "passive"))
      (node (ref "J3") (pin "4") (pinfunction "4_4") (pintype "passive"))
      (node (ref "J3") (pin "6") (pinfunction "6_6") (pintype "passive"))
      (node (ref "J5") (pin "2") (pinfunction "2_2") (pintype "passive"))
      (node (ref "R11") (pin "1") (pinfunction "1_1") (pintype "passive"))
      (node (ref "U2") (pin "1") (pinfunction "VOUT_1") (pintype "power_in"))
      (node (ref "U3") (pin "6") (pinfunction "VIN_6") (pintype "power_in"))
    )
    (net (code "149") (name "VIN") (class "Default")
      (node (ref "C57") (pin "1") (pinfunction "1_1") (pintype "passive"))
      (node (ref "C60") (pin "1") (pinfunction "1_1") (pintype "passive"))
      (node (ref "C64") (pin "1") (pinfunction "1_1") (pintype "passive"))
      (node (ref "D3") (pin "CATHODE") (pinfunction "CATHODE_CATHODE") (pintype "bidirectional"))
      (node (ref "D4") (pin "CATHODE") (pinfunction "CATHODE_CATHODE") (pintype "bidirectional"))
      (node (ref "D7") (pin "CATHODE") (pinfunction "CATHODE_CATHODE") (pintype "bidirectional"))
      (node (ref "U14") (pin "1") (pinfunction "VBUS_1") (pintype "power_in"))
      (node (ref "U14") (pin "24") (pinfunction "VBUS_24") (pintype "passive"))
    )
    (net (code "150") (name "VPOE") (class "Default")
      (node (ref "D3") (pin "ANODE") (pinfunction "ANODE_ANODE") (pintype "bidirectional"))
      (node (ref "J14") (pin "1") (pinfunction "1_1") (pintype "passive"))
    )
    (net (code "151") (name "VREG_1P8") (class "Default")
      (node (ref "R22") (pin "2") (pinfunction "2_2") (pintype "bidirectional"))
      (node (ref "TP3") (pin "P$1") (pinfunction "1_P$1") (pintype "bidirectional"))
    )
    (net (code "152") (name "VUSB") (class "Default")
      (node (ref "F1") (pin "P$2") (pinfunction "2_P$2") (pintype "bidirectional"))
      (node (ref "R61") (pin "1") (pinfunction "1_1") (pintype "passive"))
    )
    (net (code "153") (name "VUSB1") (class "Default")
      (node (ref "D4") (pin "ANODE") (pinfunction "ANODE_ANODE") (pintype "bidirectional"))
      (node (ref "J1") (pin "16") (pinfunction "P$16_16") (pintype "bidirectional"))
      (node (ref "R61") (pin "2") (pinfunction "2_2") (pintype "passive"))
    )
    (net (code "154") (name "unconnected-(DEBUG-Pad7)") (class "Default")
      (node (ref "DEBUG") (pin "7") (pinfunction "7_7") (pintype "bidirectional"))
    )
    (net (code "155") (name "unconnected-(DEBUG-Pad8)") (class "Default")
      (node (ref "DEBUG") (pin "8") (pinfunction "8_8") (pintype "bidirectional"))
    )
    (net (code "156") (name "unconnected-(J3-Pad30)") (class "Default")
      (node (ref "J3") (pin "30") (pinfunction "30_30") (pintype "passive"))
    )
    (net (code "157") (name "unconnected-(J3-Pad32)") (class "Default")
      (node (ref "J3") (pin "32") (pinfunction "32_32") (pintype "passive"))
    )
    (net (code "158") (name "unconnected-(J3-Pad60)") (class "Default")
      (node (ref "J3") (pin "60") (pinfunction "60_60") (pintype "passive"))
    )
    (net (code "159") (name "unconnected-(RJ45-NC-PadR7)") (class "Default")
      (node (ref "RJ45") (pin "R7") (pinfunction "NC_R7") (pintype "bidirectional"))
    )
    (net (code "160") (name "unconnected-(RJ45-NC-PadR8)") (class "Default")
      (node (ref "RJ45") (pin "R8") (pinfunction "NC_R8") (pintype "bidirectional"))
    )
    (net (code "161") (name "unconnected-(S1-Pad1)") (class "Default")
      (node (ref "S1") (pin "1") (pinfunction "1_1") (pintype "bidirectional"))
    )
    (net (code "162") (name "unconnected-(S1-Pad4)") (class "Default")
      (node (ref "S1") (pin "4") (pinfunction "4_4") (pintype "bidirectional"))
    )
    (net (code "163") (name "unconnected-(S4-Pad1)") (class "Default")
      (node (ref "S4") (pin "1") (pinfunction "1_1") (pintype "bidirectional"))
    )
    (net (code "164") (name "unconnected-(S4-Pad4)") (class "Default")
      (node (ref "S4") (pin "4") (pinfunction "4_4") (pintype "bidirectional"))
    )
    (net (code "165") (name "unconnected-(U1-DNC-Pad7)") (class "Default")
      (node (ref "U1") (pin "7") (pinfunction "DNC_7") (pintype "passive"))
    )
    (net (code "166") (name "unconnected-(U1-DUPLED-Pad26)") (class "Default")
      (node (ref "U1") (pin "26") (pinfunction "DUPLED_26") (pintype "passive"))
    )
    (net (code "167") (name "unconnected-(U1-NC-Pad12)") (class "Default")
      (node (ref "U1") (pin "12") (pinfunction "NC_12") (pintype "passive"))
    )
    (net (code "168") (name "unconnected-(U1-NC-Pad13)") (class "Default")
      (node (ref "U1") (pin "13") (pinfunction "NC_13") (pintype "passive"))
    )
    (net (code "169") (name "unconnected-(U1-NC-Pad46)") (class "Default")
      (node (ref "U1") (pin "46") (pinfunction "NC_46") (pintype "passive"))
    )
    (net (code "170") (name "unconnected-(U1-NC-Pad47)") (class "Default")
      (node (ref "U1") (pin "47") (pinfunction "NC_47") (pintype "passive"))
    )
    (net (code "171") (name "unconnected-(U1-SPDLED-Pad24)") (class "Default")
      (node (ref "U1") (pin "24") (pinfunction "SPDLED_24") (pintype "passive"))
    )
    (net (code "172") (name "unconnected-(U1-VBG-Pad18)") (class "Default")
      (node (ref "U1") (pin "18") (pinfunction "VBG_18") (pintype "passive"))
    )
    (net (code "173") (name "unconnected-(U2-FLG-Pad3)") (class "Default")
      (node (ref "U2") (pin "3") (pinfunction "FLG_3") (pintype "bidirectional"))
    )
    (net (code "174") (name "unconnected-(X1-Pad1)") (class "Default")
      (node (ref "X1") (pin "1") (pinfunction "1_1") (pintype "passive"))
    )
    (net (code "175") (name "unconnected-(X3-Pad1)") (class "Default")
      (node (ref "X3") (pin "1") (pinfunction "1_1") (pintype "passive"))
    )
    (net (code "176") (name "unconnected-(X4-1-DAT2-Pad1)") (class "Default")
      (node (ref "X4") (pin "1") (pinfunction "1-DAT2_1") (pintype "bidirectional"))
    )
    (net (code "177") (name "unconnected-(X4-8-DAT1-Pad8)") (class "Default")
      (node (ref "X4") (pin "8") (pinfunction "8-DAT1_8") (pintype "bidirectional"))
    )
    (net (code "178") (name "{slash}RESET") (class "Default")
      (node (ref "C24") (pin "2") (pinfunction "P$2_2") (pintype "passive"))
      (node (ref "J1") (pin "34") (pinfunction "P$34_34") (pintype "bidirectional"))
      (node (ref "J3") (pin "20") (pinfunction "20_20") (pintype "passive"))
      (node (ref "R1") (pin "1") (pinfunction "1_1") (pintype "bidirectional"))
      (node (ref "RESET") (pin "3") (pinfunction "P$3_3") (pintype "bidirectional"))
      (node (ref "RESET") (pin "4") (pinfunction "P$4_4") (pintype "bidirectional"))
      (node (ref "Z4") (pin "2") (pinfunction "2_2") (pintype "passive"))
    )
    (net (code "179") (name "{slash}REST") (class "Default")
      (node (ref "DEBUG") (pin "10") (pinfunction "10_10") (pintype "bidirectional"))
      (node (ref "P4") (pin "P$2") (pinfunction "TP_P$2") (pintype "bidirectional"))
      (node (ref "U$12") (pin "P$1") (pinfunction "TP_P$1") (pintype "bidirectional"))
    )
    (net (code "180") (name "~{CE}") (class "Default")
      (node (ref "R10") (pin "2") (pinfunction "2_2") (pintype "passive"))
      (node (ref "U14") (pin "9") (pinfunction "~{CE}_9") (pintype "output"))
    )
    (net (code "181") (name "~{ETH_INT}") (class "Default")
      (node (ref "J35") (pin "15") (pinfunction "15_15") (pintype "passive"))
      (node (ref "R25") (pin "1") (pinfunction "1_1") (pintype "passive"))
      (node (ref "U1") (pin "36") (pinfunction "INT_N_36") (pintype "passive"))
    )
    (net (code "182") (name "~{FUEL-INT}") (class "Default")
      (node (ref "J35") (pin "17") (pinfunction "17_17") (pintype "passive"))
      (node (ref "R2") (pin "2") (pinfunction "2_2") (pintype "passive"))
      (node (ref "U13") (pin "5") (pinfunction "ALT_5") (pintype "bidirectional"))
      (node (ref "U14") (pin "7") (pinfunction "INT_7") (pintype "bidirectional"))
    )
    (net (code "183") (name "~{RESET}") (class "Default")
      (node (ref "C30") (pin "2") (pinfunction "P$2_2") (pintype "passive"))
      (node (ref "R49") (pin "1") (pinfunction "1_1") (pintype "passive"))
      (node (ref "R56") (pin "1") (pinfunction "1_1") (pintype "passive"))
      (node (ref "U1") (pin "37") (pinfunction "RST_N_37") (pintype "passive"))
    )
  )
)
